# AJMG_2550XD_Silver_Jubilee.net
KiCad netlist of a schematic drawn in Altium Designer
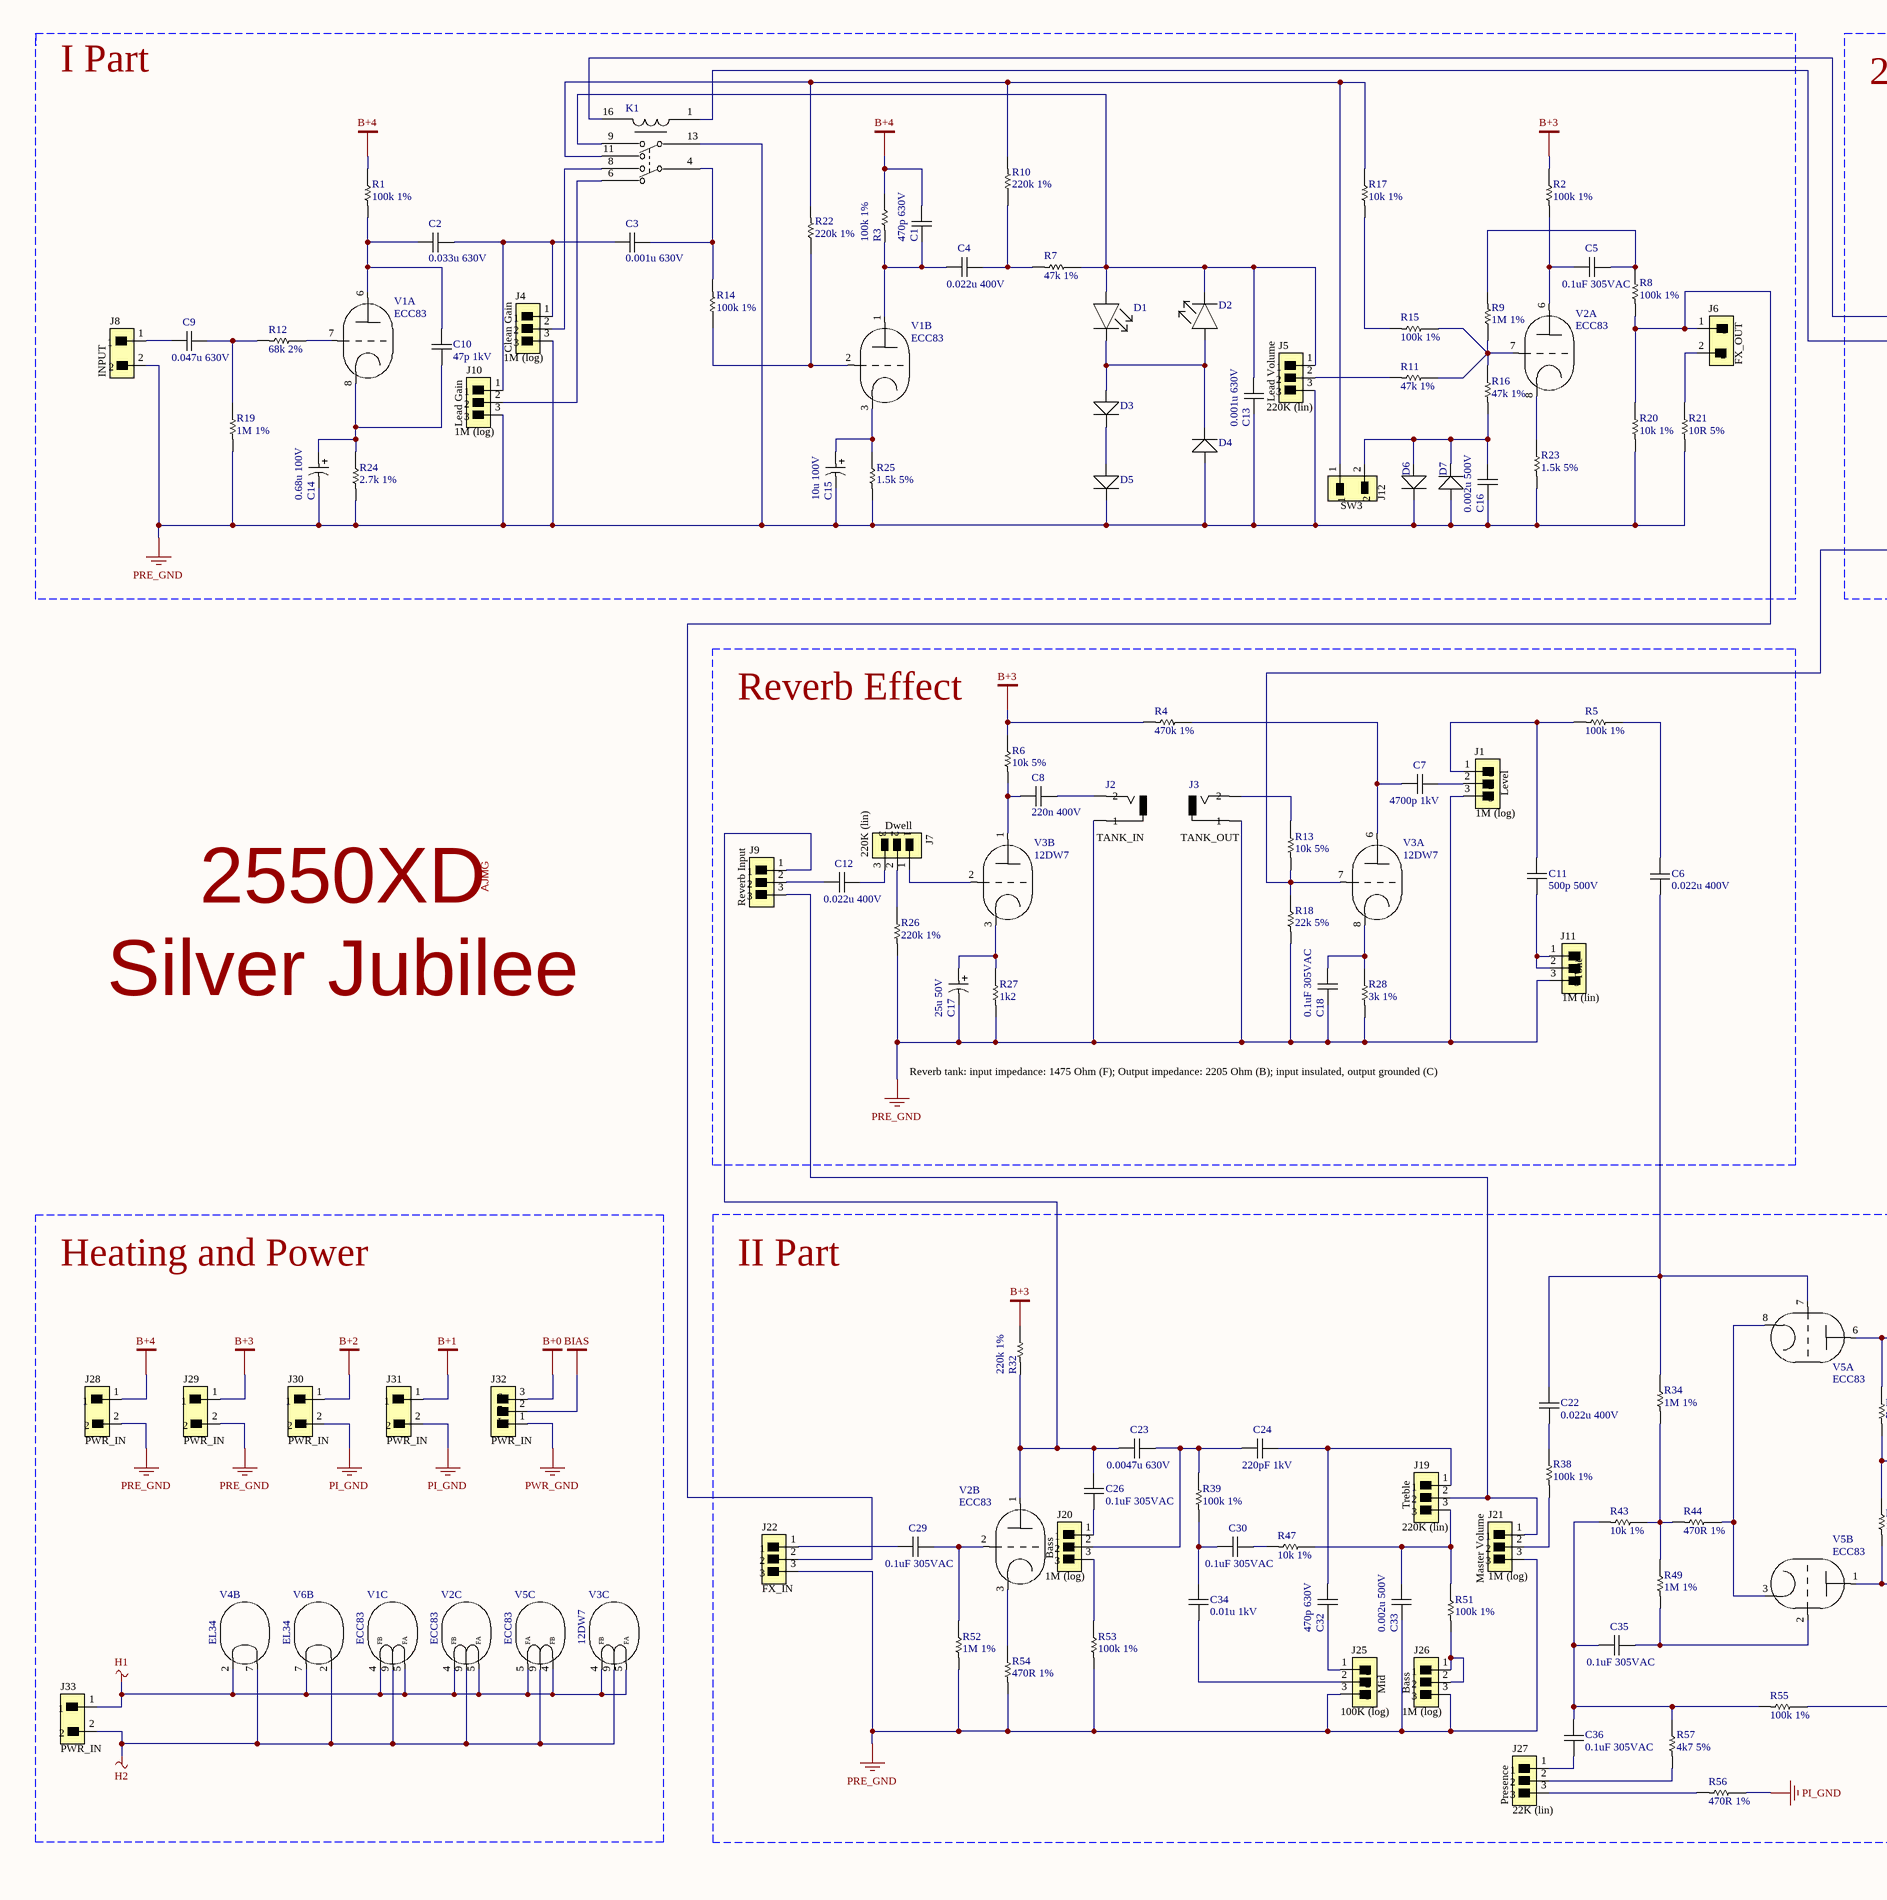
[diagram p0: AJMG 2550XD Silver Jubilee.SchDoc, left]
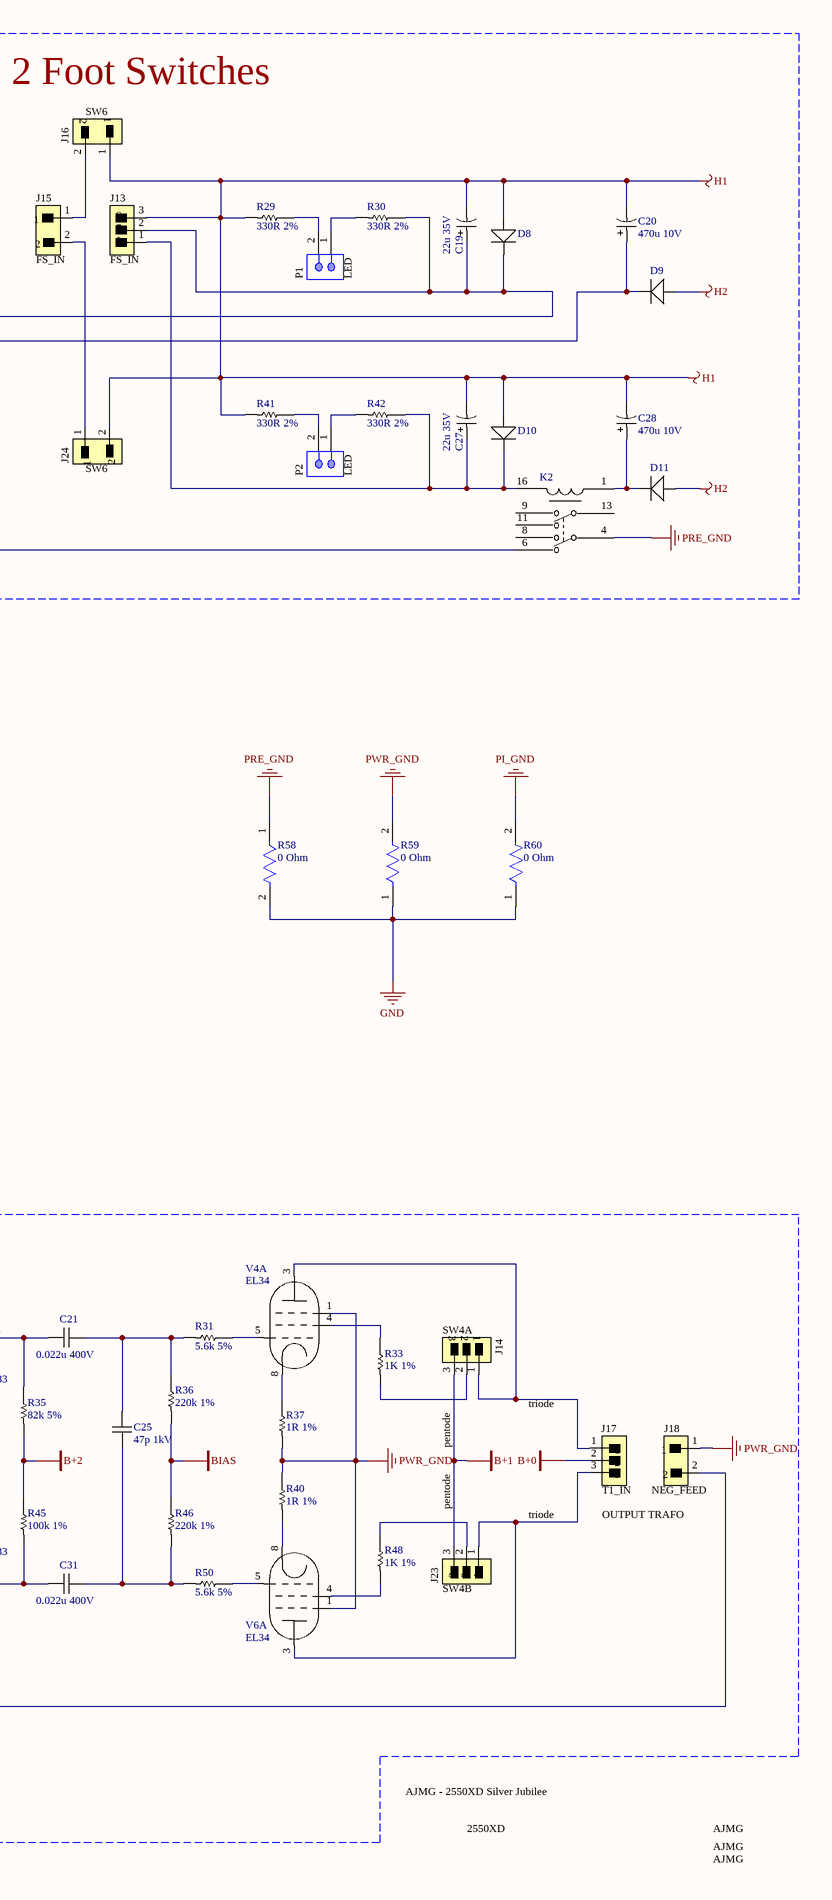
[diagram p1: AJMG 2550XD Silver Jubilee.SchDoc, right]

(export (version "E")
  (design (tool "Eeschema 10.0.6"))
  (components
    (comp (ref "C1")
      (value "470p 630V")
      (footprint "C_THT_5mm_7.2x4.5_NOT_POLARISED")
      (description "CAP FILM THT 7.2x4.5 470pF 630V 10%")
      (fields
        (field (name "MANUFACTURER") "WIMA")
        (field (name "MANUFACTURER PART NUMBER") "FKP2J004701D00KSSD")
      )
      (libsource (lib "Schematic Library - AJMG 2550XD Silver Jubilee") (part "FKP2J004701D00KSSD"))
    )
    (comp (ref "C2")
      (value "0.033u 630V")
      (footprint "C_THT_7.5mm_10.5x5_NOT_POLARISED")
      (description "CAP FILM THT 10.5x5 0.033uF 630V 5%")
      (fields
        (field (name "MANUFACTURER") "Wurth Elektronik")
        (field (name "MANUFACTURER PART NUMBER") "890303322005CS")
      )
      (libsource (lib "Schematic Library - AJMG 2550XD Silver Jubilee") (part "890303322005CS"))
    )
    (comp (ref "C3")
      (value "0.001u 630V")
      (footprint "C_THT_5mm_7.2x4.5_NOT_POLARISED")
      (description "CAP FILM THT 7.2x4.5 0.001uF 630V 10%")
      (fields
        (field (name "MANUFACTURER") "WIMA")
        (field (name "MANUFACTURER PART NUMBER") "FKP2J011001D00KI00")
      )
      (libsource (lib "Schematic Library - AJMG 2550XD Silver Jubilee") (part "FKP2J011001D00KI00"))
    )
    (comp (ref "C4")
      (value "0.022u 400V")
      (footprint "C_THT_10mm_13x5_NOT_POLARISED")
      (description "CAP FILM THT 13x4 0.022uF 400V 10%")
      (fields
        (field (name "MANUFACTURER") "WIMA")
        (field (name "MANUFACTURER PART NUMBER") "MKP4G022203C00KSSD")
      )
      (libsource (lib "Schematic Library - AJMG 2550XD Silver Jubilee") (part "MKP4G022203C00KSSD"))
    )
    (comp (ref "C5")
      (value "0.1uF 305VAC")
      (footprint "C_THT_10mm_13x5.5_NOT_POLARISED")
      (description "CAP FILM THT 13x6 0.1uF 305V(AC) 10%")
      (fields
        (field (name "MANUFACTURER") "Cornell Dubilier")
        (field (name "MANUFACTURER PART NUMBER") "MPX104K305D")
      )
      (libsource (lib "Schematic Library - AJMG 2550XD Silver Jubilee") (part "MPX104K305D"))
    )
    (comp (ref "C6")
      (value "0.022u 400V")
      (footprint "C_THT_10mm_13x5_NOT_POLARISED")
      (description "CAP FILM THT 13x4 0.022uF 400V 10%")
      (fields
        (field (name "MANUFACTURER") "WIMA")
        (field (name "MANUFACTURER PART NUMBER") "MKP4G022203C00KSSD")
      )
      (libsource (lib "Schematic Library - AJMG 2550XD Silver Jubilee") (part "MKP4G022203C00KSSD"))
    )
    (comp (ref "C7")
      (value "4700p 1kV")
      (footprint "C_THT_10mm_13x5_NOT_POLARISED")
      (description "CAP FILM THT 13x4 4700pF 1kV 10%")
      (fields
        (field (name "MANUFACTURER") "WIMA")
        (field (name "MANUFACTURER PART NUMBER") "MKP10-4700/1KV/10P10")
      )
      (libsource (lib "Schematic Library - AJMG 2550XD Silver Jubilee") (part "MKP10-4700/1KV/10P10"))
    )
    (comp (ref "C8")
      (value "220n 400V")
      (footprint "C_THT_15mm_18x5_NOT_POLARISED")
      (description "CAP FILM THT 18x5 220nF 400V 10%")
      (fields
        (field (name "MANUFACTURER") "Wurth Elektronik")
        (field (name "MANUFACTURER PART NUMBER") "890283425002CS")
      )
      (libsource (lib "Schematic Library - AJMG 2550XD Silver Jubilee") (part "890283425002CS"))
    )
    (comp (ref "C9")
      (value "0.047u 630V")
      (footprint "C_THT_7.5mm_10.5x6_NOT_POLARISED")
      (description "CAP FILM THT 10.5x6 0.047uF 630V 10%")
      (fields
        (field (name "MANUFACTURER") "Wurth Elektronik")
        (field (name "MANUFACTURER PART NUMBER") "890303422005CS")
      )
      (libsource (lib "Schematic Library - AJMG 2550XD Silver Jubilee") (part "890303422005CS"))
    )
    (comp (ref "C10")
      (value "47p 1kV")
      (footprint "C_THT_15mm_16.3x4.8_NOT_POLARISED")
      (description "CAP MICA THT 16.3x4.8 47pF 1kV 5%")
      (fields
        (field (name "MANUFACTURER") "Cornell Dubilier")
        (field (name "MANUFACTURER PART NUMBER") "CDV19EF470JO3F")
      )
      (libsource (lib "Schematic Library - AJMG 2550XD Silver Jubilee") (part "CDV19EF470JO3F"))
    )
    (comp (ref "C11")
      (value "500p 500V")
      (footprint "C_THT_9mm_16.25x5_NOT_POLARISED")
      (description "CAP MICA THT 16.3x5 500pF 500V 5%")
      (fields
        (field (name "MANUFACTURER") "Cornell Dubilier")
        (field (name "MANUFACTURER PART NUMBER") "CD19FD501JO3F")
      )
      (libsource (lib "Schematic Library - AJMG 2550XD Silver Jubilee") (part "CD19FD501JO3F"))
    )
    (comp (ref "C12")
      (value "0.022u 400V")
      (footprint "C_THT_10mm_13x5_NOT_POLARISED")
      (description "CAP FILM THT 13x4 0.022uF 400V 10%")
      (fields
        (field (name "MANUFACTURER") "WIMA")
        (field (name "MANUFACTURER PART NUMBER") "MKP4G022203C00KSSD")
      )
      (libsource (lib "Schematic Library - AJMG 2550XD Silver Jubilee") (part "MKP4G022203C00KSSD"))
    )
    (comp (ref "C13")
      (value "0.001u 630V")
      (footprint "C_THT_5mm_7.2x4.5_NOT_POLARISED")
      (description "CAP FILM THT 7.2x4.5 0.001uF 630V 10%")
      (fields
        (field (name "MANUFACTURER") "WIMA")
        (field (name "MANUFACTURER PART NUMBER") "FKP2J011001D00KI00")
      )
      (libsource (lib "Schematic Library - AJMG 2550XD Silver Jubilee") (part "FKP2J011001D00KI00"))
    )
    (comp (ref "C14")
      (value "0.68u 100V")
      (footprint "C_THT_2mm_D5H11_POLARISED")
      (description "CAP ALUM THT D5xH11 0.68uF 100V 20%")
      (fields
        (field (name "MANUFACTURER") "Nichicon")
        (field (name "MANUFACTURER PART NUMBER") "UKL2AR68KDD1TA")
      )
      (libsource (lib "Schematic Library - AJMG 2550XD Silver Jubilee") (part "UKL2AR68KDD1TA"))
    )
    (comp (ref "C15")
      (value "10u 100V")
      (footprint "C_THT_2mm_D5H11_POLARISED")
      (description "CAP ALUM THT D5xH11 10uF 100V 20%")
      (fields
        (field (name "MANUFACTURER") "Rubycon")
        (field (name "MANUFACTURER PART NUMBER") "100PK10MEFC5X11")
      )
      (libsource (lib "Schematic Library - AJMG 2550XD Silver Jubilee") (part "100PK10MEFC5X11"))
    )
    (comp (ref "C16")
      (value "0.002u 500V")
      (footprint "C_THT_8mm_16x5_NOT_POLARISED")
      (description "CAP MICA THT AxB 0.002uF 500V 5%")
      (libsource (lib "Schematic Library - AJMG 2550XD Silver Jubilee") (part "TAD SILVER MICA CAPS"))
    )
    (comp (ref "C17")
      (value "25u 50V")
      (footprint "C_THT_22.5mm_D6.35xH17.45_AXIAL_POLARISED")
      (description "CAP ALUM THT AXIAL D6.35xH17.45 25uF 50V 20%")
      (fields (field (name "MANUFACTURER") "Vishay") (field (name "MANUFACTURER PART NUMBER") "TVA1306"))
      (libsource (lib "Schematic Library - AJMG 2550XD Silver Jubilee") (part "TVA1306"))
    )
    (comp (ref "C18")
      (value "0.1uF 305VAC")
      (footprint "C_THT_10mm_13x5.5_NOT_POLARISED")
      (description "CAP FILM THT 13x6 0.1uF 305V(AC) 10%")
      (fields
        (field (name "MANUFACTURER") "Cornell Dubilier")
        (field (name "MANUFACTURER PART NUMBER") "MPX104K305D")
      )
      (libsource (lib "Schematic Library - AJMG 2550XD Silver Jubilee") (part "MPX104K305D"))
    )
    (comp (ref "C19")
      (value "22u 35V")
      (footprint "C_THT_2mm_D5H11_POLARISED")
      (description "CAP ALUM THT D5xH11 22uF 35V 20%")
      (fields
        (field (name "MANUFACTURER PART NUMBER") "860010572003")
        (field (name "MANUFACTURER") "Wurth Elektronik")
      )
      (libsource (lib "Schematic Library - AJMG 2550XD Silver Jubilee") (part "860010572003"))
    )
    (comp (ref "C20")
      (value "470u 10V")
      (footprint "C_THT_2.5mm_D6.3H11_POLARISED")
      (description "CAP ALUM THT D6.3xH11 470uF 10V 20%")
      (fields
        (field (name "MANUFACTURER PART NUMBER") "860010273011")
        (field (name "MANUFACTURER") "Wurth Elektronik")
      )
      (libsource (lib "Schematic Library - AJMG 2550XD Silver Jubilee") (part "860010273011"))
    )
    (comp (ref "C21")
      (value "0.022u 400V")
      (footprint "C_THT_10mm_13x5_NOT_POLARISED")
      (description "CAP FILM THT 13x4 0.022uF 400V 10%")
      (fields
        (field (name "MANUFACTURER") "WIMA")
        (field (name "MANUFACTURER PART NUMBER") "MKP4G022203C00KSSD")
      )
      (libsource (lib "Schematic Library - AJMG 2550XD Silver Jubilee") (part "MKP4G022203C00KSSD"))
    )
    (comp (ref "C22")
      (value "0.022u 400V")
      (footprint "C_THT_10mm_13x5_NOT_POLARISED")
      (description "CAP FILM THT 13x4 0.022uF 400V 10%")
      (fields
        (field (name "MANUFACTURER") "WIMA")
        (field (name "MANUFACTURER PART NUMBER") "MKP4G022203C00KSSD")
      )
      (libsource (lib "Schematic Library - AJMG 2550XD Silver Jubilee") (part "MKP4G022203C00KSSD"))
    )
    (comp (ref "C23")
      (value "0.0047u 630V")
      (footprint "C_THT_5mm_7.2x6.5_NOT_POLARISED")
      (description "CAP FILM THT 7.2x6.5 0.0047uF 630V 5%")
      (fields
        (field (name "MANUFACTURER") "WIMA")
        (field (name "MANUFACTURER PART NUMBER") "FKP2J014701I00JSSD")
      )
      (libsource (lib "Schematic Library - AJMG 2550XD Silver Jubilee") (part "FKP2J014701I00JSSD"))
    )
    (comp (ref "C24")
      (value "220pF 1kV")
      (footprint "C_THT_7.5mm_10.9x3.8_NOT_POLARISED")
      (description "CAP MICA THT 10.9x3.8 220pF 1kV 5%")
      (fields
        (field (name "MANUFACTURER") "Cornell Dubilier")
        (field (name "MANUFACTURER PART NUMBER") "CDV16FF221JO3F")
      )
      (libsource (lib "Schematic Library - AJMG 2550XD Silver Jubilee") (part "CDV16FF221JO3F"))
    )
    (comp (ref "C25")
      (value "47p 1kV")
      (footprint "C_THT_15mm_16.3x4.8_NOT_POLARISED")
      (description "CAP MICA THT 16.3x4.8 47pF 1kV 5%")
      (fields
        (field (name "MANUFACTURER") "Cornell Dubilier")
        (field (name "MANUFACTURER PART NUMBER") "CDV19EF470JO3F")
      )
      (libsource (lib "Schematic Library - AJMG 2550XD Silver Jubilee") (part "CDV19EF470JO3F"))
    )
    (comp (ref "C26")
      (value "0.1uF 305VAC")
      (footprint "C_THT_10mm_13x5.5_NOT_POLARISED")
      (description "CAP FILM THT 13x6 0.1uF 305V(AC) 10%")
      (fields
        (field (name "MANUFACTURER") "Cornell Dubilier")
        (field (name "MANUFACTURER PART NUMBER") "MPX104K305D")
      )
      (libsource (lib "Schematic Library - AJMG 2550XD Silver Jubilee") (part "MPX104K305D"))
    )
    (comp (ref "C27")
      (value "22u 35V")
      (footprint "C_THT_2mm_D5H11_POLARISED")
      (description "CAP ALUM THT D5xH11 22uF 35V 20%")
      (fields
        (field (name "MANUFACTURER PART NUMBER") "860010572003")
        (field (name "MANUFACTURER") "Wurth Elektronik")
      )
      (libsource (lib "Schematic Library - AJMG 2550XD Silver Jubilee") (part "860010572003"))
    )
    (comp (ref "C28")
      (value "470u 10V")
      (footprint "C_THT_2.5mm_D6.3H11_POLARISED")
      (description "CAP ALUM THT D6.3xH11 470uF 10V 20%")
      (fields
        (field (name "MANUFACTURER PART NUMBER") "860010273011")
        (field (name "MANUFACTURER") "Wurth Elektronik")
      )
      (libsource (lib "Schematic Library - AJMG 2550XD Silver Jubilee") (part "860010273011"))
    )
    (comp (ref "C29")
      (value "0.1uF 305VAC")
      (footprint "C_THT_10mm_13x5.5_NOT_POLARISED")
      (description "CAP FILM THT 13x6 0.1uF 305V(AC) 10%")
      (fields
        (field (name "MANUFACTURER") "Cornell Dubilier")
        (field (name "MANUFACTURER PART NUMBER") "MPX104K305D")
      )
      (libsource (lib "Schematic Library - AJMG 2550XD Silver Jubilee") (part "MPX104K305D"))
    )
    (comp (ref "C30")
      (value "0.1uF 305VAC")
      (footprint "C_THT_10mm_13x5.5_NOT_POLARISED")
      (description "CAP FILM THT 13x6 0.1uF 305V(AC) 10%")
      (fields
        (field (name "MANUFACTURER") "Cornell Dubilier")
        (field (name "MANUFACTURER PART NUMBER") "MPX104K305D")
      )
      (libsource (lib "Schematic Library - AJMG 2550XD Silver Jubilee") (part "MPX104K305D"))
    )
    (comp (ref "C31")
      (value "0.022u 400V")
      (footprint "C_THT_10mm_13x5_NOT_POLARISED")
      (description "CAP FILM THT 13x4 0.022uF 400V 10%")
      (fields
        (field (name "MANUFACTURER") "WIMA")
        (field (name "MANUFACTURER PART NUMBER") "MKP4G022203C00KSSD")
      )
      (libsource (lib "Schematic Library - AJMG 2550XD Silver Jubilee") (part "MKP4G022203C00KSSD"))
    )
    (comp (ref "C32")
      (value "470p 630V")
      (footprint "C_THT_5mm_7.2x4.5_NOT_POLARISED")
      (description "CAP FILM THT 7.2x4.5 470pF 630V 10%")
      (fields
        (field (name "MANUFACTURER") "WIMA")
        (field (name "MANUFACTURER PART NUMBER") "FKP2J004701D00KSSD")
      )
      (libsource (lib "Schematic Library - AJMG 2550XD Silver Jubilee") (part "FKP2J004701D00KSSD"))
    )
    (comp (ref "C33")
      (value "0.002u 500V")
      (footprint "C_THT_8mm_16x5_NOT_POLARISED")
      (description "CAP MICA THT AxB 0.002uF 500V 5%")
      (libsource (lib "Schematic Library - AJMG 2550XD Silver Jubilee") (part "TAD SILVER MICA CAPS"))
    )
    (comp (ref "C34")
      (value "0.01u 1kV")
      (footprint "C_THT_7.5mm_10.5x6_NOT_POLARISED")
      (description "CAP FILM THT 10.5x6 0.01uF 1kV 10%")
      (fields
        (field (name "MANUFACTURER") "Wurth Elektronik")
        (field (name "MANUFACTURER PART NUMBER") "890493422002CS")
      )
      (libsource (lib "Schematic Library - AJMG 2550XD Silver Jubilee") (part "890493422002CS"))
    )
    (comp (ref "C35")
      (value "0.1uF 305VAC")
      (footprint "C_THT_10mm_13x5.5_NOT_POLARISED")
      (description "CAP FILM THT 13x6 0.1uF 305V(AC) 10%")
      (fields
        (field (name "MANUFACTURER") "Cornell Dubilier")
        (field (name "MANUFACTURER PART NUMBER") "MPX104K305D")
      )
      (libsource (lib "Schematic Library - AJMG 2550XD Silver Jubilee") (part "MPX104K305D"))
    )
    (comp (ref "C36")
      (value "0.1uF 305VAC")
      (footprint "C_THT_10mm_13x5.5_NOT_POLARISED")
      (description "CAP FILM THT 13x6 0.1uF 305V(AC) 10%")
      (fields
        (field (name "MANUFACTURER") "Cornell Dubilier")
        (field (name "MANUFACTURER PART NUMBER") "MPX104K305D")
      )
      (libsource (lib "Schematic Library - AJMG 2550XD Silver Jubilee") (part "MPX104K305D"))
    )
    (comp (ref "D1")
      (value "LTST-C930CKT")
      (footprint "D_LTST-C930CKT")
      (description "DIODE LED SMD")
      (fields
        (field (name "OCTOPART") "https://octopart.com/ltst-c930kskt-lite-on-549925")
        (field (name "MANUFACTURER PART NUMBER") "LTST-C930KSKT")
      )
      (libsource (lib "Schematic Library - AJMG 2550XD Silver Jubilee") (part "LTST-C930CKT"))
    )
    (comp (ref "D2")
      (value "LTST-C930CKT")
      (footprint "D_LTST-C930CKT")
      (description "DIODE LED SMD")
      (fields
        (field (name "OCTOPART") "https://octopart.com/ltst-c930kskt-lite-on-549925")
        (field (name "MANUFACTURER PART NUMBER") "LTST-C930KSKT")
      )
      (libsource (lib "Schematic Library - AJMG 2550XD Silver Jubilee") (part "LTST-C930CKT"))
    )
    (comp (ref "D3")
      (value "1N4007-T")
      (footprint "D_1N4007-T")
      (description "DIODE\r\n1.0 A Rectifier, 8 pF, 1000 V, -65 to 150 degC, 2-Pin DO-41 Plastic, RoHS, Tape and Reel")
      (fields (field (name "MANUFACTURER") "Diodes Inc"))
      (libsource (lib "Schematic Library - AJMG 2550XD Silver Jubilee") (part "1N4007-T"))
    )
    (comp (ref "D4")
      (value "1N4007-T")
      (footprint "D_1N4007-T")
      (description "DIODE\r\n1.0 A Rectifier, 8 pF, 1000 V, -65 to 150 degC, 2-Pin DO-41 Plastic, RoHS, Tape and Reel")
      (fields (field (name "MANUFACTURER") "Diodes Inc"))
      (libsource (lib "Schematic Library - AJMG 2550XD Silver Jubilee") (part "1N4007-T"))
    )
    (comp (ref "D5")
      (value "1N4007-T")
      (footprint "D_1N4007-T")
      (description "DIODE\r\n1.0 A Rectifier, 8 pF, 1000 V, -65 to 150 degC, 2-Pin DO-41 Plastic, RoHS, Tape and Reel")
      (fields (field (name "MANUFACTURER") "Diodes Inc"))
      (libsource (lib "Schematic Library - AJMG 2550XD Silver Jubilee") (part "1N4007-T"))
    )
    (comp (ref "D6")
      (value "1N4007-T")
      (footprint "D_1N4007-T")
      (description "DIODE\r\n1.0 A Rectifier, 8 pF, 1000 V, -65 to 150 degC, 2-Pin DO-41 Plastic, RoHS, Tape and Reel")
      (fields (field (name "MANUFACTURER") "Diodes Inc"))
      (libsource (lib "Schematic Library - AJMG 2550XD Silver Jubilee") (part "1N4007-T"))
    )
    (comp (ref "D7")
      (value "1N4007-T")
      (footprint "D_1N4007-T")
      (description "DIODE\r\n1.0 A Rectifier, 8 pF, 1000 V, -65 to 150 degC, 2-Pin DO-41 Plastic, RoHS, Tape and Reel")
      (fields (field (name "MANUFACTURER") "Diodes Inc"))
      (libsource (lib "Schematic Library - AJMG 2550XD Silver Jubilee") (part "1N4007-T"))
    )
    (comp (ref "D8")
      (value "1N4007-T")
      (footprint "D_1N4007-T")
      (description "DIODE\r\n1.0 A Rectifier, 8 pF, 1000 V, -65 to 150 degC, 2-Pin DO-41 Plastic, RoHS, Tape and Reel")
      (fields (field (name "MANUFACTURER") "Diodes Inc"))
      (libsource (lib "Schematic Library - AJMG 2550XD Silver Jubilee") (part "1N4007-T"))
    )
    (comp (ref "D9")
      (value "1N4007-T")
      (footprint "D_1N4007-T")
      (description "DIODE\r\n1.0 A Rectifier, 8 pF, 1000 V, -65 to 150 degC, 2-Pin DO-41 Plastic, RoHS, Tape and Reel")
      (fields (field (name "MANUFACTURER") "Diodes Inc"))
      (libsource (lib "Schematic Library - AJMG 2550XD Silver Jubilee") (part "1N4007-T"))
    )
    (comp (ref "D10")
      (value "1N4007-T")
      (footprint "D_1N4007-T")
      (description "DIODE\r\n1.0 A Rectifier, 8 pF, 1000 V, -65 to 150 degC, 2-Pin DO-41 Plastic, RoHS, Tape and Reel")
      (fields (field (name "MANUFACTURER") "Diodes Inc"))
      (libsource (lib "Schematic Library - AJMG 2550XD Silver Jubilee") (part "1N4007-T"))
    )
    (comp (ref "D11")
      (value "1N4007-T")
      (footprint "D_1N4007-T")
      (description "DIODE\r\n1.0 A Rectifier, 8 pF, 1000 V, -65 to 150 degC, 2-Pin DO-41 Plastic, RoHS, Tape and Reel")
      (fields (field (name "MANUFACTURER") "Diodes Inc"))
      (libsource (lib "Schematic Library - AJMG 2550XD Silver Jubilee") (part "1N4007-T"))
    )
    (comp (ref "J1")
      (value "43650-0320")
      (footprint "CONN HEADER VERT 3POS 3MM")
      (description "CONN HEADER VERT 3POS 3MM")
      (fields
        (field (name "MANUFACTURER") "Molex")
        (field (name "OCTOPART") "https://octopart.com/43650-0320-molex-7670312")
      )
      (libsource (lib "") (part "CMP-04776-000004-1_1"))
    )
    (comp (ref "J2")
      (value "RCJ-021")
      (footprint "CONN_CUI_RCJ-021")
      (description "CONN RCA JACK MONO 3.2MM PCB")
      (fields (field (name "MANUFACTURER") "CUI"))
      (libsource (lib "Schematic Library - AJMG 2550XD Silver Jubilee") (part "RCJ-021"))
    )
    (comp (ref "J3")
      (value "RCJ-021")
      (footprint "CONN_CUI_RCJ-021")
      (description "CONN RCA JACK MONO 3.2MM PCB")
      (fields (field (name "MANUFACTURER") "CUI"))
      (libsource (lib "") (part "RCJ-021_1"))
    )
    (comp (ref "J4")
      (value "43650-0320")
      (footprint "CONN HEADER VERT 3POS 3MM")
      (description "CONN HEADER VERT 3POS 3MM")
      (fields
        (field (name "MANUFACTURER") "Molex")
        (field (name "OCTOPART") "https://octopart.com/43650-0320-molex-7670312")
      )
      (libsource (lib "Schematic Library - AJMG 2550XD Silver Jubilee") (part "CMP-04776-000004-1"))
    )
    (comp (ref "J5")
      (value "43650-0320")
      (footprint "CONN HEADER VERT 3POS 3MM")
      (description "CONN HEADER VERT 3POS 3MM")
      (fields
        (field (name "MANUFACTURER") "Molex")
        (field (name "OCTOPART") "https://octopart.com/43650-0320-molex-7670312")
      )
      (libsource (lib "Schematic Library - AJMG 2550XD Silver Jubilee") (part "CMP-04776-000004-1"))
    )
    (comp (ref "J6")
      (value "43650-0229")
      (footprint "CONN HEADER VERT 2POS 3MM")
      (description "CONN HEADER VERT 2POS 3MM")
      (fields
        (field (name "OCTOPART") "https://octopart.com/43650-0229-molex-7652326")
        (field (name "MANUFACTURER") "Molex")
      )
      (libsource (lib "") (part "CMP-04776-000041-1_1"))
    )
    (comp (ref "J7")
      (value "43650-0320")
      (footprint "CONN HEADER VERT 3POS 3MM")
      (description "CONN HEADER VERT 3POS 3MM")
      (fields
        (field (name "MANUFACTURER") "Molex")
        (field (name "OCTOPART") "https://octopart.com/43650-0320-molex-7670312")
      )
      (libsource (lib "") (part "CMP-04776-000004-1_1"))
    )
    (comp (ref "J8")
      (value "43650-0229")
      (footprint "CONN HEADER VERT 2POS 3MM")
      (description "CONN HEADER VERT 2POS 3MM")
      (fields
        (field (name "OCTOPART") "https://octopart.com/43650-0229-molex-7652326")
        (field (name "MANUFACTURER") "Molex")
      )
      (libsource (lib "Schematic Library - AJMG 2550XD Silver Jubilee") (part "CMP-04776-000041-1"))
    )
    (comp (ref "J9")
      (value "43650-0320")
      (footprint "CONN HEADER VERT 3POS 3MM")
      (description "CONN HEADER VERT 3POS 3MM")
      (fields
        (field (name "MANUFACTURER") "Molex")
        (field (name "OCTOPART") "https://octopart.com/43650-0320-molex-7670312")
      )
      (libsource (lib "Schematic Library - AJMG 2550XD Silver Jubilee") (part "CMP-04776-000004-1"))
    )
    (comp (ref "J10")
      (value "43650-0320")
      (footprint "CONN HEADER VERT 3POS 3MM")
      (description "CONN HEADER VERT 3POS 3MM")
      (fields
        (field (name "MANUFACTURER") "Molex")
        (field (name "OCTOPART") "https://octopart.com/43650-0320-molex-7670312")
      )
      (libsource (lib "Schematic Library - AJMG 2550XD Silver Jubilee") (part "CMP-04776-000004-1"))
    )
    (comp (ref "J11")
      (value "43650-0320")
      (footprint "CONN HEADER VERT 3POS 3MM")
      (description "CONN HEADER VERT 3POS 3MM")
      (fields
        (field (name "MANUFACTURER") "Molex")
        (field (name "OCTOPART") "https://octopart.com/43650-0320-molex-7670312")
      )
      (libsource (lib "") (part "CMP-04776-000004-1_1"))
    )
    (comp (ref "J12")
      (value "43650-0229")
      (footprint "CONN HEADER VERT 2POS 3MM")
      (description "CONN HEADER VERT 2POS 3MM")
      (fields
        (field (name "OCTOPART") "https://octopart.com/43650-0229-molex-7652326")
        (field (name "MANUFACTURER") "Molex")
      )
      (libsource (lib "") (part "CMP-04776-000041-1_2"))
    )
    (comp (ref "J13")
      (value "43650-0320")
      (footprint "CONN HEADER VERT 3POS 3MM")
      (description "CONN HEADER VERT 3POS 3MM")
      (fields
        (field (name "MANUFACTURER") "Molex")
        (field (name "OCTOPART") "https://octopart.com/43650-0320-molex-7670312")
      )
      (libsource (lib "") (part "CMP-04776-000004-1_2"))
    )
    (comp (ref "J14")
      (value "43650-0320")
      (footprint "CONN HEADER VERT 3POS 3MM")
      (description "CONN HEADER VERT 3POS 3MM")
      (fields
        (field (name "MANUFACTURER") "Molex")
        (field (name "OCTOPART") "https://octopart.com/43650-0320-molex-7670312")
      )
      (libsource (lib "") (part "CMP-04776-000004-1_1"))
    )
    (comp (ref "J15")
      (value "43650-0229")
      (footprint "CONN HEADER VERT 2POS 3MM")
      (description "CONN HEADER VERT 2POS 3MM")
      (fields
        (field (name "OCTOPART") "https://octopart.com/43650-0229-molex-7652326")
        (field (name "MANUFACTURER") "Molex")
      )
      (libsource (lib "Schematic Library - AJMG 2550XD Silver Jubilee") (part "CMP-04776-000041-1"))
    )
    (comp (ref "J16")
      (value "43650-0229")
      (footprint "CONN HEADER VERT 2POS 3MM")
      (description "CONN HEADER VERT 2POS 3MM")
      (fields
        (field (name "OCTOPART") "https://octopart.com/43650-0229-molex-7652326")
        (field (name "MANUFACTURER") "Molex")
      )
      (libsource (lib "") (part "CMP-04776-000041-1_1"))
    )
    (comp (ref "J17")
      (value "43650-0320")
      (footprint "CONN HEADER VERT 3POS 3MM")
      (description "CONN HEADER VERT 3POS 3MM")
      (fields
        (field (name "MANUFACTURER") "Molex")
        (field (name "OCTOPART") "https://octopart.com/43650-0320-molex-7670312")
      )
      (libsource (lib "") (part "CMP-04776-000004-1_1"))
    )
    (comp (ref "J18")
      (value "43650-0229")
      (footprint "CONN HEADER VERT 2POS 3MM")
      (description "CONN HEADER VERT 2POS 3MM")
      (fields
        (field (name "OCTOPART") "https://octopart.com/43650-0229-molex-7652326")
        (field (name "MANUFACTURER") "Molex")
      )
      (libsource (lib "Schematic Library - AJMG 2550XD Silver Jubilee") (part "CMP-04776-000041-1"))
    )
    (comp (ref "J19")
      (value "43650-0320")
      (footprint "CONN HEADER VERT 3POS 3MM")
      (description "CONN HEADER VERT 3POS 3MM")
      (fields
        (field (name "MANUFACTURER") "Molex")
        (field (name "OCTOPART") "https://octopart.com/43650-0320-molex-7670312")
      )
      (libsource (lib "Schematic Library - AJMG 2550XD Silver Jubilee") (part "CMP-04776-000004-1"))
    )
    (comp (ref "J20")
      (value "43650-0320")
      (footprint "CONN HEADER VERT 3POS 3MM")
      (description "CONN HEADER VERT 3POS 3MM")
      (fields
        (field (name "MANUFACTURER") "Molex")
        (field (name "OCTOPART") "https://octopart.com/43650-0320-molex-7670312")
      )
      (libsource (lib "Schematic Library - AJMG 2550XD Silver Jubilee") (part "CMP-04776-000004-1"))
    )
    (comp (ref "J21")
      (value "43650-0320")
      (footprint "CONN HEADER VERT 3POS 3MM")
      (description "CONN HEADER VERT 3POS 3MM")
      (fields
        (field (name "MANUFACTURER") "Molex")
        (field (name "OCTOPART") "https://octopart.com/43650-0320-molex-7670312")
      )
      (libsource (lib "Schematic Library - AJMG 2550XD Silver Jubilee") (part "CMP-04776-000004-1"))
    )
    (comp (ref "J22")
      (value "43650-0320")
      (footprint "CONN HEADER VERT 3POS 3MM")
      (description "CONN HEADER VERT 3POS 3MM")
      (fields
        (field (name "MANUFACTURER") "Molex")
        (field (name "OCTOPART") "https://octopart.com/43650-0320-molex-7670312")
      )
      (libsource (lib "Schematic Library - AJMG 2550XD Silver Jubilee") (part "CMP-04776-000004-1"))
    )
    (comp (ref "J23")
      (value "43650-0320")
      (footprint "CONN HEADER VERT 3POS 3MM")
      (description "CONN HEADER VERT 3POS 3MM")
      (fields
        (field (name "MANUFACTURER") "Molex")
        (field (name "OCTOPART") "https://octopart.com/43650-0320-molex-7670312")
      )
      (libsource (lib "Schematic Library - AJMG 2550XD Silver Jubilee") (part "CMP-04776-000004-1"))
    )
    (comp (ref "J24")
      (value "43650-0229")
      (footprint "CONN HEADER VERT 2POS 3MM")
      (description "CONN HEADER VERT 2POS 3MM")
      (fields
        (field (name "OCTOPART") "https://octopart.com/43650-0229-molex-7652326")
        (field (name "MANUFACTURER") "Molex")
      )
      (libsource (lib "") (part "CMP-04776-000041-1_2"))
    )
    (comp (ref "J25")
      (value "43650-0320")
      (footprint "CONN HEADER VERT 3POS 3MM")
      (description "CONN HEADER VERT 3POS 3MM")
      (fields
        (field (name "MANUFACTURER") "Molex")
        (field (name "OCTOPART") "https://octopart.com/43650-0320-molex-7670312")
      )
      (libsource (lib "") (part "CMP-04776-000004-1_1"))
    )
    (comp (ref "J26")
      (value "43650-0320")
      (footprint "CONN HEADER VERT 3POS 3MM")
      (description "CONN HEADER VERT 3POS 3MM")
      (fields
        (field (name "MANUFACTURER") "Molex")
        (field (name "OCTOPART") "https://octopart.com/43650-0320-molex-7670312")
      )
      (libsource (lib "Schematic Library - AJMG 2550XD Silver Jubilee") (part "CMP-04776-000004-1"))
    )
    (comp (ref "J27")
      (value "43650-0320")
      (footprint "CONN HEADER VERT 3POS 3MM")
      (description "CONN HEADER VERT 3POS 3MM")
      (fields
        (field (name "MANUFACTURER") "Molex")
        (field (name "OCTOPART") "https://octopart.com/43650-0320-molex-7670312")
      )
      (libsource (lib "Schematic Library - AJMG 2550XD Silver Jubilee") (part "CMP-04776-000004-1"))
    )
    (comp (ref "J28")
      (value "43650-0229")
      (footprint "CONN HEADER VERT 2POS 3MM")
      (description "CONN HEADER VERT 2POS 3MM")
      (fields
        (field (name "OCTOPART") "https://octopart.com/43650-0229-molex-7652326")
        (field (name "MANUFACTURER") "Molex")
      )
      (libsource (lib "Schematic Library - AJMG 2550XD Silver Jubilee") (part "CMP-04776-000041-1"))
    )
    (comp (ref "J29")
      (value "43650-0229")
      (footprint "CONN HEADER VERT 2POS 3MM")
      (description "CONN HEADER VERT 2POS 3MM")
      (fields
        (field (name "OCTOPART") "https://octopart.com/43650-0229-molex-7652326")
        (field (name "MANUFACTURER") "Molex")
      )
      (libsource (lib "Schematic Library - AJMG 2550XD Silver Jubilee") (part "CMP-04776-000041-1"))
    )
    (comp (ref "J30")
      (value "43650-0229")
      (footprint "CONN HEADER VERT 2POS 3MM")
      (description "CONN HEADER VERT 2POS 3MM")
      (fields
        (field (name "OCTOPART") "https://octopart.com/43650-0229-molex-7652326")
        (field (name "MANUFACTURER") "Molex")
      )
      (libsource (lib "Schematic Library - AJMG 2550XD Silver Jubilee") (part "CMP-04776-000041-1"))
    )
    (comp (ref "J31")
      (value "43650-0229")
      (footprint "CONN HEADER VERT 2POS 3MM")
      (description "CONN HEADER VERT 2POS 3MM")
      (fields
        (field (name "OCTOPART") "https://octopart.com/43650-0229-molex-7652326")
        (field (name "MANUFACTURER") "Molex")
      )
      (libsource (lib "Schematic Library - AJMG 2550XD Silver Jubilee") (part "CMP-04776-000041-1"))
    )
    (comp (ref "J32")
      (value "43650-0320")
      (footprint "CONN HEADER VERT 3POS 3MM")
      (description "CONN HEADER VERT 3POS 3MM")
      (fields
        (field (name "MANUFACTURER") "Molex")
        (field (name "OCTOPART") "https://octopart.com/43650-0320-molex-7670312")
      )
      (libsource (lib "") (part "CMP-04776-000004-1_2"))
    )
    (comp (ref "J33")
      (value "43650-0229")
      (footprint "CONN HEADER VERT 2POS 3MM")
      (description "CONN HEADER VERT 2POS 3MM")
      (fields
        (field (name "OCTOPART") "https://octopart.com/43650-0229-molex-7652326")
        (field (name "MANUFACTURER") "Molex")
      )
      (libsource (lib "Schematic Library - AJMG 2550XD Silver Jubilee") (part "CMP-04776-000041-1"))
    )
    (comp (ref "K1")
      (value "9-1393792-3")
      (footprint "RELAY_V23105A5301A201")
      (description "RELAY TELECOM DPDT 3A 5V")
      (fields
        (field (name "MANUFACTURER") "TE Connectivity")
        (field (name "OCTOPART") "https://octopart.com/9-1393792-3-te+connectivity-41192813")
      )
      (libsource (lib "Schematic Library - AJMG 2550XD Silver Jubilee") (part "CMP-03395-000111-1"))
    )
    (comp (ref "K2")
      (value "9-1393792-3")
      (footprint "RELAY_V23105A5301A201")
      (description "RELAY TELECOM DPDT 3A 5V")
      (fields
        (field (name "MANUFACTURER") "TE Connectivity")
        (field (name "OCTOPART") "https://octopart.com/9-1393792-3-te+connectivity-41192813")
      )
      (libsource (lib "Schematic Library - AJMG 2550XD Silver Jubilee") (part "CMP-03395-000111-1"))
    )
    (comp (ref "P1")
      (value "22-27-2021")
      (footprint "MOLX-22-27-2021_V")
      (fields (field (name "MANUFACTURER") "Molex") (field (name "PARTNUMBER") "0022272021"))
      (libsource (lib "Altium Content Vault") (part "CN-1P-M-R2"))
    )
    (comp (ref "P2")
      (value "22-27-2021")
      (footprint "MOLX-22-27-2021_V")
      (fields (field (name "MANUFACTURER") "Molex") (field (name "PARTNUMBER") "0022272021"))
      (libsource (lib "Altium Content Vault") (part "CN-1P-M-R2"))
    )
    (comp (ref "R1")
      (value "100k 1%")
      (footprint "R_2010")
      (description "RES SMD 2010 100K 1% 1W")
      (fields
        (field (name "MANUFACTURER") "Bourns")
        (field (name "MANUFACTURER PART NUMBER") "CMP2010-FX-1003ELF")
      )
      (libsource (lib "Schematic Library - AJMG 2550XD Silver Jubilee") (part "CMP2010-FX-1003ELF"))
    )
    (comp (ref "R2")
      (value "100k 1%")
      (footprint "R_2010")
      (description "RES SMD 2010 100K 1% 1W")
      (fields
        (field (name "MANUFACTURER") "Bourns")
        (field (name "MANUFACTURER PART NUMBER") "CMP2010-FX-1003ELF")
      )
      (libsource (lib "Schematic Library - AJMG 2550XD Silver Jubilee") (part "CMP2010-FX-1003ELF"))
    )
    (comp (ref "R3")
      (value "100k 1%")
      (footprint "R_2010")
      (description "RES SMD 2010 100K 1% 1W")
      (fields
        (field (name "MANUFACTURER") "Bourns")
        (field (name "MANUFACTURER PART NUMBER") "CMP2010-FX-1003ELF")
      )
      (libsource (lib "Schematic Library - AJMG 2550XD Silver Jubilee") (part "CMP2010-FX-1003ELF"))
    )
    (comp (ref "R4")
      (value "470k 1%")
      (footprint "R_2010")
      (description "RES SMD 2010 470K 1% 1W")
      (libsource (lib "Schematic Library - AJMG 2550XD Silver Jubilee") (part "CRM2010-FX-4703ELF"))
    )
    (comp (ref "R5")
      (value "100k 1%")
      (footprint "R_2010")
      (description "RES SMD 2010 100K 1% 1W")
      (fields
        (field (name "MANUFACTURER") "Bourns")
        (field (name "MANUFACTURER PART NUMBER") "CMP2010-FX-1003ELF")
      )
      (libsource (lib "Schematic Library - AJMG 2550XD Silver Jubilee") (part "CMP2010-FX-1003ELF"))
    )
    (comp (ref "R6")
      (value "10k 5%")
      (footprint "R_2512")
      (description "RES SMD 2512 10K 5% 3W")
      (fields
        (field (name "MANUFACTURER") "Bourns")
        (field (name "MANUFACTURER PART NUMBER") "CHP2512-JW-103ELF")
      )
      (libsource (lib "Schematic Library - AJMG 2550XD Silver Jubilee") (part "CHP2512-JW-103ELF"))
    )
    (comp (ref "R7")
      (value "47k 1%")
      (footprint "R_2512")
      (description "RES SMD 2512 47K 1% 1.5W")
      (fields
        (field (name "MANUFACTURER") "Bourns")
        (field (name "MANUFACTURER PART NUMBER") "CMP2512-FX-4702ELF")
      )
      (libsource (lib "Schematic Library - AJMG 2550XD Silver Jubilee") (part "CMP2512-FX-4702ELF"))
    )
    (comp (ref "R8")
      (value "100k 1%")
      (footprint "R_2010")
      (description "RES SMD 2010 100K 1% 1W")
      (fields
        (field (name "MANUFACTURER") "Bourns")
        (field (name "MANUFACTURER PART NUMBER") "CMP2010-FX-1003ELF")
      )
      (libsource (lib "Schematic Library - AJMG 2550XD Silver Jubilee") (part "CMP2010-FX-1003ELF"))
    )
    (comp (ref "R9")
      (value "1M 1%")
      (footprint "R_2010")
      (description "RES SMD 2010 1M 1% 1W")
      (fields
        (field (name "MANUFACTURER") "Bourns")
        (field (name "MANUFACTURER PART NUMBER") "CMP2010-FX-1004ELF")
      )
      (libsource (lib "Schematic Library - AJMG 2550XD Silver Jubilee") (part "CMP2010-FX-1004ELF"))
    )
    (comp (ref "R10")
      (value "220k 1%")
      (footprint "R_2010")
      (description "RES SMD 2010 220K 1% 1/2W")
      (fields
        (field (name "MANUFACTURER") "Bourns JW Miller")
        (field (name "MANUFACTURER PART NUMBER") "CHV2010-FX-2203ELF")
      )
      (libsource (lib "Schematic Library - AJMG 2550XD Silver Jubilee") (part "CHV2010-FX-2203ELF"))
    )
    (comp (ref "R11")
      (value "47k 1%")
      (footprint "R_2512")
      (description "RES SMD 2512 47K 1% 1.5W")
      (fields
        (field (name "MANUFACTURER") "Bourns")
        (field (name "MANUFACTURER PART NUMBER") "CMP2512-FX-4702ELF")
      )
      (libsource (lib "Schematic Library - AJMG 2550XD Silver Jubilee") (part "CMP2512-FX-4702ELF"))
    )
    (comp (ref "R12")
      (value "68k 2%")
      (footprint "R_MELF_0204")
      (description "RES SMD 0204 68K 2% 400mW")
      (fields
        (field (name "MANUFACTURER") "Vishay Beyschlag")
        (field (name "MANUFACTURER PART NUMBER") "CMA02040X6802GB300")
      )
      (libsource (lib "Schematic Library - AJMG 2550XD Silver Jubilee") (part "CMA02040X6802GB300"))
    )
    (comp (ref "R13")
      (value "10k 5%")
      (footprint "R_2512")
      (description "RES SMD 2512 10K 5% 3W")
      (fields
        (field (name "MANUFACTURER") "Bourns")
        (field (name "MANUFACTURER PART NUMBER") "CHP2512-JW-103ELF")
      )
      (libsource (lib "Schematic Library - AJMG 2550XD Silver Jubilee") (part "CHP2512-JW-103ELF"))
    )
    (comp (ref "R14")
      (value "100k 1%")
      (footprint "R_2010")
      (description "RES SMD 2010 100K 1% 1W")
      (fields
        (field (name "MANUFACTURER") "Bourns")
        (field (name "MANUFACTURER PART NUMBER") "CMP2010-FX-1003ELF")
      )
      (libsource (lib "Schematic Library - AJMG 2550XD Silver Jubilee") (part "CMP2010-FX-1003ELF"))
    )
    (comp (ref "R15")
      (value "100k 1%")
      (footprint "R_2010")
      (description "RES SMD 2010 100K 1% 1W")
      (fields
        (field (name "MANUFACTURER") "Bourns")
        (field (name "MANUFACTURER PART NUMBER") "CMP2010-FX-1003ELF")
      )
      (libsource (lib "Schematic Library - AJMG 2550XD Silver Jubilee") (part "CMP2010-FX-1003ELF"))
    )
    (comp (ref "R16")
      (value "47k 1%")
      (footprint "R_2512")
      (description "RES SMD 2512 47K 1% 1.5W")
      (fields
        (field (name "MANUFACTURER") "Bourns")
        (field (name "MANUFACTURER PART NUMBER") "CMP2512-FX-4702ELF")
      )
      (libsource (lib "Schematic Library - AJMG 2550XD Silver Jubilee") (part "CMP2512-FX-4702ELF"))
    )
    (comp (ref "R17")
      (value "10k 1%")
      (footprint "R_2010")
      (description "RES SMD 2010 10K 1% 1W")
      (fields
        (field (name "MANUFACTURER") "Bourns")
        (field (name "MANUFACTURER PART NUMBER") "CMP2010-FX-1002ELF")
      )
      (libsource (lib "Schematic Library - AJMG 2550XD Silver Jubilee") (part "CMP2010-FX-1002ELF"))
    )
    (comp (ref "R18")
      (value "22k 5%")
      (footprint "R_2512")
      (description "RES SMD 2512 22K 5% 1W")
      (fields
        (field (name "MANUFACTURER") "Bourns")
        (field (name "MANUFACTURER PART NUMBER") "CR2512-JW-223ELF")
      )
      (libsource (lib "Schematic Library - AJMG 2550XD Silver Jubilee") (part "CR2512-JW-223ELF"))
    )
    (comp (ref "R19")
      (value "1M 1%")
      (footprint "R_2010")
      (description "RES SMD 2010 1M 1% 1W")
      (fields
        (field (name "MANUFACTURER") "Bourns")
        (field (name "MANUFACTURER PART NUMBER") "CMP2010-FX-1004ELF")
      )
      (libsource (lib "Schematic Library - AJMG 2550XD Silver Jubilee") (part "CMP2010-FX-1004ELF"))
    )
    (comp (ref "R20")
      (value "10k 1%")
      (footprint "R_2010")
      (description "RES SMD 2010 10K 1% 1W")
      (fields
        (field (name "MANUFACTURER") "Bourns")
        (field (name "MANUFACTURER PART NUMBER") "CMP2010-FX-1002ELF")
      )
      (libsource (lib "Schematic Library - AJMG 2550XD Silver Jubilee") (part "CMP2010-FX-1002ELF"))
    )
    (comp (ref "R21")
      (value "10R 5%")
      (footprint "R_2616_MOLDED")
      (description "RES SMD 2616 10R 5% 2W SMW2")
      (fields
        (field (name "MANUFACTURER") "TE Connectivity")
        (field (name "MANUFACTURER PART NUMBER") "SMW210RJT")
      )
      (libsource (lib "Schematic Library - AJMG 2550XD Silver Jubilee") (part "SMW210RJT"))
    )
    (comp (ref "R22")
      (value "220k 1%")
      (footprint "R_2010")
      (description "RES SMD 2010 220K 1% 1/2W")
      (fields
        (field (name "MANUFACTURER") "Bourns JW Miller")
        (field (name "MANUFACTURER PART NUMBER") "CHV2010-FX-2203ELF")
      )
      (libsource (lib "Schematic Library - AJMG 2550XD Silver Jubilee") (part "CHV2010-FX-2203ELF"))
    )
    (comp (ref "R23")
      (value "1.5k 5%")
      (footprint "R_2512")
      (description "RES SMD 2512 1.5k 5% 1W")
      (fields
        (field (name "MANUFACTURER") "Bourns")
        (field (name "MANUFACTURER PART NUMBER") "CR2512-JW-152ELF")
      )
      (libsource (lib "Schematic Library - AJMG 2550XD Silver Jubilee") (part "CR2512-JW-152ELF"))
    )
    (comp (ref "R24")
      (value "2.7k 1%")
      (footprint "R_2512")
      (description "RES SMD 2512 2.7K 1% 1.5W")
      (fields
        (field (name "MANUFACTURER") "Bourns")
        (field (name "MANUFACTURER PART NUMBER") "CMP2512AFX-2701ELF")
      )
      (libsource (lib "Schematic Library - AJMG 2550XD Silver Jubilee") (part "CMP2512AFX-2701ELF"))
    )
    (comp (ref "R25")
      (value "1.5k 5%")
      (footprint "R_2512")
      (description "RES SMD 2512 1.5k 5% 1W")
      (fields
        (field (name "MANUFACTURER") "Bourns")
        (field (name "MANUFACTURER PART NUMBER") "CR2512-JW-152ELF")
      )
      (libsource (lib "Schematic Library - AJMG 2550XD Silver Jubilee") (part "CR2512-JW-152ELF"))
    )
    (comp (ref "R26")
      (value "220k 1%")
      (footprint "R_2010")
      (description "RES SMD 2010 220K 1% 1/2W")
      (fields
        (field (name "MANUFACTURER") "Bourns JW Miller")
        (field (name "MANUFACTURER PART NUMBER") "CHV2010-FX-2203ELF")
      )
      (libsource (lib "Schematic Library - AJMG 2550XD Silver Jubilee") (part "CHV2010-FX-2203ELF"))
    )
    (comp (ref "R27")
      (value "1k2")
      (footprint "R_2512")
      (description "RES SMD 2512 1.2k 5% 1W")
      (fields
        (field (name "MANUFACTURER") "Bourns")
        (field (name "MANUFACTURER PART NUMBER") "CR2512-JW-122ELF")
      )
      (libsource (lib "Schematic Library - AJMG 2550XD Silver Jubilee") (part "CR2512-JW-122ELF"))
    )
    (comp (ref "R28")
      (value "3k 1%")
      (footprint "R_2512")
      (description "RES SMD 2512 3k 1% 1W")
      (fields
        (field (name "MANUFACTURER") "Bourns")
        (field (name "MANUFACTURER PART NUMBER") "CR2512-FX-3001ELF")
      )
      (libsource (lib "Schematic Library - AJMG 2550XD Silver Jubilee") (part "CR2512-FX-3001ELF"))
    )
    (comp (ref "R29")
      (value "330R 2%")
      (footprint "R_MELF_0207")
      (description "RES SMD 0207 330R 2% 1W")
      (fields
        (field (name "MANUFACTURER") "Vishay Beyschlag")
        (field (name "MANUFACTURER PART NUMBER") "CMB02070X3300GB200")
      )
      (libsource (lib "Schematic Library - AJMG 2550XD Silver Jubilee") (part "CMB02070X3300GB200"))
    )
    (comp (ref "R30")
      (value "330R 2%")
      (footprint "R_MELF_0207")
      (description "RES SMD 0207 330R 2% 1W")
      (fields
        (field (name "MANUFACTURER") "Vishay Beyschlag")
        (field (name "MANUFACTURER PART NUMBER") "CMB02070X3300GB200")
      )
      (libsource (lib "Schematic Library - AJMG 2550XD Silver Jubilee") (part "CMB02070X3300GB200"))
    )
    (comp (ref "R31")
      (value "5.6k 5%")
      (footprint "R_2512")
      (description "RES SMD 2512 5.6K 5% 1W")
      (fields
        (field (name "MANUFACTURER") "Bourns")
        (field (name "MANUFACTURER PART NUMBER") "CR2512-JW-562ELF")
      )
      (libsource (lib "Schematic Library - AJMG 2550XD Silver Jubilee") (part "CR2512-JW-562ELF"))
    )
    (comp (ref "R32")
      (value "220k 1%")
      (footprint "R_2010")
      (description "RES SMD 2010 220K 1% 1/2W")
      (fields
        (field (name "MANUFACTURER") "Bourns JW Miller")
        (field (name "MANUFACTURER PART NUMBER") "CHV2010-FX-2203ELF")
      )
      (libsource (lib "Schematic Library - AJMG 2550XD Silver Jubilee") (part "CHV2010-FX-2203ELF"))
    )
    (comp (ref "R33")
      (value "1K 1%")
      (footprint "R_3550")
      (description "RES SMD 3550 1K 1% 5W")
      (fields
        (field (name "MANUFACTURER") "TE Connectivity")
        (field (name "MANUFACTURER PART NUMBER") "35501K0FT")
      )
      (libsource (lib "Schematic Library - AJMG 2550XD Silver Jubilee") (part "35501K0FT"))
    )
    (comp (ref "R34")
      (value "1M 1%")
      (footprint "R_2010")
      (description "RES SMD 2010 1M 1% 1W")
      (fields
        (field (name "MANUFACTURER") "Bourns")
        (field (name "MANUFACTURER PART NUMBER") "CMP2010-FX-1004ELF")
      )
      (libsource (lib "Schematic Library - AJMG 2550XD Silver Jubilee") (part "CMP2010-FX-1004ELF"))
    )
    (comp (ref "R35")
      (value "82k 5%")
      (footprint "R_2512")
      (description "RES SMD 2512 82K 5% 2W")
      (fields
        (field (name "MANUFACTURER") "Bourns")
        (field (name "MANUFACTURER PART NUMBER") "CRM2512-JW-823ELF")
      )
      (libsource (lib "Schematic Library - AJMG 2550XD Silver Jubilee") (part "CRM2512-JW-823ELF"))
    )
    (comp (ref "R36")
      (value "220k 1%")
      (footprint "R_2010")
      (description "RES SMD 2010 220K 1% 1/2W")
      (fields
        (field (name "MANUFACTURER") "Bourns JW Miller")
        (field (name "MANUFACTURER PART NUMBER") "CHV2010-FX-2203ELF")
      )
      (libsource (lib "Schematic Library - AJMG 2550XD Silver Jubilee") (part "CHV2010-FX-2203ELF"))
    )
    (comp (ref "R37")
      (value "1R 1%")
      (footprint "R_4527_MOLDED")
      (description "RES SMD 4527 1R 1% 2W")
      (fields
        (field (name "MANUFACTURER") "Vishay Dale")
        (field (name "MANUFACTURER PART NUMBER") "WSC00021R000FEA")
      )
      (libsource (lib "Schematic Library - AJMG 2550XD Silver Jubilee") (part "WSC00021R000FEA"))
    )
    (comp (ref "R38")
      (value "100k 1%")
      (footprint "R_2010")
      (description "RES SMD 2010 100K 1% 1W")
      (fields
        (field (name "MANUFACTURER") "Bourns")
        (field (name "MANUFACTURER PART NUMBER") "CMP2010-FX-1003ELF")
      )
      (libsource (lib "Schematic Library - AJMG 2550XD Silver Jubilee") (part "CMP2010-FX-1003ELF"))
    )
    (comp (ref "R39")
      (value "100k 1%")
      (footprint "R_2010")
      (description "RES SMD 2010 100K 1% 1W")
      (fields
        (field (name "MANUFACTURER") "Bourns")
        (field (name "MANUFACTURER PART NUMBER") "CMP2010-FX-1003ELF")
      )
      (libsource (lib "Schematic Library - AJMG 2550XD Silver Jubilee") (part "CMP2010-FX-1003ELF"))
    )
    (comp (ref "R40")
      (value "1R 1%")
      (footprint "R_4527_MOLDED")
      (description "RES SMD 4527 1R 1% 2W")
      (fields
        (field (name "MANUFACTURER") "Vishay Dale")
        (field (name "MANUFACTURER PART NUMBER") "WSC00021R000FEA")
      )
      (libsource (lib "Schematic Library - AJMG 2550XD Silver Jubilee") (part "WSC00021R000FEA"))
    )
    (comp (ref "R41")
      (value "330R 2%")
      (footprint "R_MELF_0207")
      (description "RES SMD 0207 330R 2% 1W")
      (fields
        (field (name "MANUFACTURER") "Vishay Beyschlag")
        (field (name "MANUFACTURER PART NUMBER") "CMB02070X3300GB200")
      )
      (libsource (lib "Schematic Library - AJMG 2550XD Silver Jubilee") (part "CMB02070X3300GB200"))
    )
    (comp (ref "R42")
      (value "330R 2%")
      (footprint "R_MELF_0207")
      (description "RES SMD 0207 330R 2% 1W")
      (fields
        (field (name "MANUFACTURER") "Vishay Beyschlag")
        (field (name "MANUFACTURER PART NUMBER") "CMB02070X3300GB200")
      )
      (libsource (lib "Schematic Library - AJMG 2550XD Silver Jubilee") (part "CMB02070X3300GB200"))
    )
    (comp (ref "R43")
      (value "10k 1%")
      (footprint "R_2010")
      (description "RES SMD 2010 10K 1% 1W")
      (fields
        (field (name "MANUFACTURER") "Bourns")
        (field (name "MANUFACTURER PART NUMBER") "CMP2010-FX-1002ELF")
      )
      (libsource (lib "Schematic Library - AJMG 2550XD Silver Jubilee") (part "CMP2010-FX-1002ELF"))
    )
    (comp (ref "R44")
      (value "470R 1%")
      (footprint "R_2512")
      (description "RES SMD 2512 470R 1% 2W")
      (fields
        (field (name "MANUFACTURER") "Bourns")
        (field (name "MANUFACTURER PART NUMBER") "CRM2512-FX-4700ELF")
      )
      (libsource (lib "Schematic Library - AJMG 2550XD Silver Jubilee") (part "CRM2512-FX-4700ELF"))
    )
    (comp (ref "R45")
      (value "100k 1%")
      (footprint "R_2010")
      (description "RES SMD 2010 100K 1% 1W")
      (fields
        (field (name "MANUFACTURER") "Bourns")
        (field (name "MANUFACTURER PART NUMBER") "CMP2010-FX-1003ELF")
      )
      (libsource (lib "Schematic Library - AJMG 2550XD Silver Jubilee") (part "CMP2010-FX-1003ELF"))
    )
    (comp (ref "R46")
      (value "220k 1%")
      (footprint "R_2010")
      (description "RES SMD 2010 220K 1% 1/2W")
      (fields
        (field (name "MANUFACTURER") "Bourns JW Miller")
        (field (name "MANUFACTURER PART NUMBER") "CHV2010-FX-2203ELF")
      )
      (libsource (lib "Schematic Library - AJMG 2550XD Silver Jubilee") (part "CHV2010-FX-2203ELF"))
    )
    (comp (ref "R47")
      (value "10k 1%")
      (footprint "R_2010")
      (description "RES SMD 2010 10K 1% 1W")
      (fields
        (field (name "MANUFACTURER") "Bourns")
        (field (name "MANUFACTURER PART NUMBER") "CMP2010-FX-1002ELF")
      )
      (libsource (lib "Schematic Library - AJMG 2550XD Silver Jubilee") (part "CMP2010-FX-1002ELF"))
    )
    (comp (ref "R48")
      (value "1K 1%")
      (footprint "R_3550")
      (description "RES SMD 3550 1K 1% 5W")
      (fields
        (field (name "MANUFACTURER") "TE Connectivity")
        (field (name "MANUFACTURER PART NUMBER") "35501K0FT")
      )
      (libsource (lib "Schematic Library - AJMG 2550XD Silver Jubilee") (part "35501K0FT"))
    )
    (comp (ref "R49")
      (value "1M 1%")
      (footprint "R_2010")
      (description "RES SMD 2010 1M 1% 1W")
      (fields
        (field (name "MANUFACTURER") "Bourns")
        (field (name "MANUFACTURER PART NUMBER") "CMP2010-FX-1004ELF")
      )
      (libsource (lib "Schematic Library - AJMG 2550XD Silver Jubilee") (part "CMP2010-FX-1004ELF"))
    )
    (comp (ref "R50")
      (value "5.6k 5%")
      (footprint "R_2512")
      (description "RES SMD 2512 5.6K 5% 1W")
      (fields
        (field (name "MANUFACTURER") "Bourns")
        (field (name "MANUFACTURER PART NUMBER") "CR2512-JW-562ELF")
      )
      (libsource (lib "Schematic Library - AJMG 2550XD Silver Jubilee") (part "CR2512-JW-562ELF"))
    )
    (comp (ref "R51")
      (value "100k 1%")
      (footprint "R_2010")
      (description "RES SMD 2010 100K 1% 1W")
      (fields
        (field (name "MANUFACTURER") "Bourns")
        (field (name "MANUFACTURER PART NUMBER") "CMP2010-FX-1003ELF")
      )
      (libsource (lib "Schematic Library - AJMG 2550XD Silver Jubilee") (part "CMP2010-FX-1003ELF"))
    )
    (comp (ref "R52")
      (value "1M 1%")
      (footprint "R_2010")
      (description "RES SMD 2010 1M 1% 1W")
      (fields
        (field (name "MANUFACTURER") "Bourns")
        (field (name "MANUFACTURER PART NUMBER") "CMP2010-FX-1004ELF")
      )
      (libsource (lib "Schematic Library - AJMG 2550XD Silver Jubilee") (part "CMP2010-FX-1004ELF"))
    )
    (comp (ref "R53")
      (value "100k 1%")
      (footprint "R_2010")
      (description "RES SMD 2010 100K 1% 1W")
      (fields
        (field (name "MANUFACTURER") "Bourns")
        (field (name "MANUFACTURER PART NUMBER") "CMP2010-FX-1003ELF")
      )
      (libsource (lib "Schematic Library - AJMG 2550XD Silver Jubilee") (part "CMP2010-FX-1003ELF"))
    )
    (comp (ref "R54")
      (value "470R 1%")
      (footprint "R_2512")
      (description "RES SMD 2512 470R 1% 2W")
      (fields
        (field (name "MANUFACTURER") "Bourns")
        (field (name "MANUFACTURER PART NUMBER") "CRM2512-FX-4700ELF")
      )
      (libsource (lib "Schematic Library - AJMG 2550XD Silver Jubilee") (part "CRM2512-FX-4700ELF"))
    )
    (comp (ref "R55")
      (value "100k 1%")
      (footprint "R_2010")
      (description "RES SMD 2010 100K 1% 1W")
      (fields
        (field (name "MANUFACTURER") "Bourns")
        (field (name "MANUFACTURER PART NUMBER") "CMP2010-FX-1003ELF")
      )
      (libsource (lib "Schematic Library - AJMG 2550XD Silver Jubilee") (part "CMP2010-FX-1003ELF"))
    )
    (comp (ref "R56")
      (value "470R 1%")
      (footprint "R_2512")
      (description "RES SMD 2512 470R 1% 2W")
      (fields
        (field (name "MANUFACTURER") "Bourns")
        (field (name "MANUFACTURER PART NUMBER") "CRM2512-FX-4700ELF")
      )
      (libsource (lib "Schematic Library - AJMG 2550XD Silver Jubilee") (part "CRM2512-FX-4700ELF"))
    )
    (comp (ref "R57")
      (value "4k7 5%")
      (footprint "R_2512_N")
      (description "RES SMD 2512 4.7k 5% 1W")
      (fields (field (name "TOLERANCE") "5 %") (field (name "POWER") "1 W"))
      (libsource (lib "Schematic Library - AJMG 2550XD Silver Jubilee") (part "CMP-1018-00090-1"))
    )
    (comp (ref "R58")
      (value "0 Ohm")
      (footprint "FP-CRCW1210-e3-IPC_B")
      (description "RES SMD 205K OHM 1% 1/2W 1992")
      (libsource (lib "Altium Content Vault") (part "1029c3af85768c4190bb7ad29bc67b5"))
    )
    (comp (ref "R59")
      (value "0 Ohm")
      (footprint "FP-CRCW1210-e3-IPC_B")
      (description "RES SMD 205K OHM 1% 1/2W 1992")
      (libsource (lib "Altium Content Vault") (part "1029c3af85768c4190bb7ad29bc67b5"))
    )
    (comp (ref "R60")
      (value "0 Ohm")
      (footprint "FP-CRCW1210-e3-IPC_B")
      (description "RES SMD 205K OHM 1% 1/2W 1992")
      (libsource (lib "Altium Content Vault") (part "1029c3af85768c4190bb7ad29bc67b5"))
    )
    (comp (ref "V1")
      (value "ECC83")
      (footprint "VT9-PT-2")
      (libsource (lib "Schematic Library - AJMG 2550XD Silver Jubilee") (part "ECC83"))
    )
    (comp (ref "V2")
      (value "ECC83")
      (footprint "VT9-PT-2")
      (libsource (lib "Schematic Library - AJMG 2550XD Silver Jubilee") (part "ECC83"))
    )
    (comp (ref "V3")
      (value "12DW7")
      (footprint "VT9-PT-2")
      (libsource (lib "Schematic Library - AJMG 2550XD Silver Jubilee") (part "12DW7"))
    )
    (comp (ref "V4") (value "EL34") (footprint "VT8-PT-2") (libsource (lib "") (part "EL34_1")))
    (comp (ref "V5") (value "ECC83") (footprint "VT9-PT-2") (libsource (lib "") (part "ECC83_1")))
    (comp (ref "V6")
      (value "EL34")
      (footprint "VT8-PT-2")
      (libsource (lib "Schematic Library - AJMG 2550XD Silver Jubilee") (part "EL34"))
    )
  )
  (nets
    (net (code "1") (name "B+0") (class "Default")
      (node (ref "J17") (pin "2") (pinfunction "2_2") (pintype "passive"))
      (node (ref "J32") (pin "3") (pinfunction "3_3") (pintype "passive"))
    )
    (net (code "2") (name "B+1") (class "Default")
      (node (ref "J14") (pin "3") (pinfunction "3_3") (pintype "passive"))
      (node (ref "J23") (pin "3") (pinfunction "3_3") (pintype "passive"))
      (node (ref "J31") (pin "1") (pinfunction "1_1") (pintype "passive"))
    )
    (net (code "3") (name "B+2") (class "Default")
      (node (ref "J30") (pin "1") (pinfunction "1_1") (pintype "passive"))
      (node (ref "R35") (pin "1") (pinfunction "1_1") (pintype "passive"))
      (node (ref "R45") (pin "2") (pinfunction "2_2") (pintype "passive"))
    )
    (net (code "4") (name "B+3") (class "Default")
      (node (ref "J29") (pin "1") (pinfunction "1_1") (pintype "passive"))
      (node (ref "R2") (pin "2") (pinfunction "2_2") (pintype "passive"))
      (node (ref "R32") (pin "2") (pinfunction "2_2") (pintype "passive"))
      (node (ref "R4") (pin "1") (pinfunction "1_1") (pintype "passive"))
      (node (ref "R6") (pin "2") (pinfunction "2_2") (pintype "passive"))
    )
    (net (code "5") (name "B+4") (class "Default")
      (node (ref "C1") (pin "2") (pinfunction "2_2") (pintype "passive"))
      (node (ref "J28") (pin "1") (pinfunction "1_1") (pintype "passive"))
      (node (ref "R1") (pin "2") (pinfunction "2_2") (pintype "passive"))
      (node (ref "R3") (pin "2") (pinfunction "2_2") (pintype "passive"))
    )
    (net (code "6") (name "BIAS") (class "Default")
      (node (ref "J32") (pin "2") (pinfunction "2_2") (pintype "passive"))
      (node (ref "R36") (pin "1") (pinfunction "1_1") (pintype "passive"))
      (node (ref "R46") (pin "2") (pinfunction "2_2") (pintype "passive"))
    )
    (net (code "7") (name "GND") (class "Default")
      (node (ref "R58") (pin "2") (pinfunction "2_2") (pintype "passive"))
      (node (ref "R59") (pin "1") (pinfunction "1_1") (pintype "passive"))
      (node (ref "R60") (pin "1") (pinfunction "1_1") (pintype "passive"))
    )
    (net (code "8") (name "H1") (class "Default")
      (node (ref "C19") (pin "2") (pinfunction "N_2") (pintype "passive"))
      (node (ref "C20") (pin "2") (pinfunction "N_2") (pintype "passive"))
      (node (ref "C27") (pin "2") (pinfunction "N_2") (pintype "passive"))
      (node (ref "C28") (pin "2") (pinfunction "N_2") (pintype "passive"))
      (node (ref "D10") (pin "1") (pinfunction "A_1") (pintype "passive"))
      (node (ref "D8") (pin "1") (pinfunction "A_1") (pintype "passive"))
      (node (ref "J13") (pin "3") (pinfunction "3_3") (pintype "passive"))
      (node (ref "J16") (pin "1") (pinfunction "1_1") (pintype "passive"))
      (node (ref "J24") (pin "2") (pinfunction "2_2") (pintype "passive"))
      (node (ref "J33") (pin "1") (pinfunction "1_1") (pintype "passive"))
      (node (ref "R29") (pin "1") (pinfunction "1_1") (pintype "passive"))
      (node (ref "R41") (pin "1") (pinfunction "1_1") (pintype "passive"))
      (node (ref "V1") (pin "4") (pinfunction "FB_4") (pintype "passive"))
      (node (ref "V1") (pin "5") (pinfunction "FA_5") (pintype "passive"))
      (node (ref "V2") (pin "4") (pinfunction "FB_4") (pintype "passive"))
      (node (ref "V2") (pin "5") (pinfunction "FA_5") (pintype "passive"))
      (node (ref "V3") (pin "4") (pinfunction "FB_4") (pintype "passive"))
      (node (ref "V3") (pin "5") (pinfunction "FA_5") (pintype "passive"))
      (node (ref "V4") (pin "2") (pinfunction "F_2") (pintype "passive"))
      (node (ref "V5") (pin "4") (pinfunction "FB_4") (pintype "passive"))
      (node (ref "V5") (pin "5") (pinfunction "FA_5") (pintype "passive"))
      (node (ref "V6") (pin "7") (pinfunction "F_7") (pintype "passive"))
    )
    (net (code "9") (name "H2") (class "Default")
      (node (ref "D11") (pin "1") (pinfunction "A_1") (pintype "passive"))
      (node (ref "D9") (pin "1") (pinfunction "A_1") (pintype "passive"))
      (node (ref "J33") (pin "2") (pinfunction "2_2") (pintype "passive"))
      (node (ref "V1") (pin "9") (pinfunction "FC_9") (pintype "passive"))
      (node (ref "V2") (pin "9") (pinfunction "FC_9") (pintype "passive"))
      (node (ref "V3") (pin "9") (pinfunction "FC_9") (pintype "passive"))
      (node (ref "V4") (pin "7") (pinfunction "F_7") (pintype "passive"))
      (node (ref "V5") (pin "9") (pinfunction "FC_9") (pintype "passive"))
      (node (ref "V6") (pin "2") (pinfunction "F_2") (pintype "passive"))
    )
    (net (code "10") (name "Net-(C2-Pad2)") (class "Default")
      (node (ref "C2") (pin "2") (pinfunction "2_2") (pintype "passive"))
      (node (ref "C3") (pin "1") (pinfunction "1_1") (pintype "passive"))
      (node (ref "J10") (pin "1") (pinfunction "1_1") (pintype "passive"))
      (node (ref "J4") (pin "1") (pinfunction "1_1") (pintype "passive"))
    )
    (net (code "11") (name "Net-(C3-Pad2)") (class "Default")
      (node (ref "C3") (pin "2") (pinfunction "2_2") (pintype "passive"))
      (node (ref "K1") (pin "4") (pinfunction "4_4") (pintype "passive"))
      (node (ref "R14") (pin "1") (pinfunction "1_1") (pintype "passive"))
    )
    (net (code "12") (name "Net-(C4-Pad2)") (class "Default")
      (node (ref "C4") (pin "2") (pinfunction "2_2") (pintype "passive"))
      (node (ref "R10") (pin "2") (pinfunction "2_2") (pintype "passive"))
      (node (ref "R7") (pin "1") (pinfunction "1_1") (pintype "passive"))
    )
    (net (code "13") (name "Net-(C5-Pad2)") (class "Default")
      (node (ref "C5") (pin "2") (pinfunction "2_2") (pintype "passive"))
      (node (ref "R8") (pin "2") (pinfunction "2_2") (pintype "passive"))
      (node (ref "R9") (pin "1") (pinfunction "1_1") (pintype "passive"))
    )
    (net (code "14") (name "Net-(C6-Pad1)") (class "Default")
      (node (ref "C6") (pin "1") (pinfunction "1_1") (pintype "passive"))
      (node (ref "R5") (pin "2") (pinfunction "2_2") (pintype "passive"))
    )
    (net (code "15") (name "Net-(C7-Pad2)") (class "Default")
      (node (ref "C7") (pin "2") (pinfunction "2_2") (pintype "passive"))
      (node (ref "J1") (pin "2") (pinfunction "2_2") (pintype "passive"))
    )
    (net (code "16") (name "Net-(C8-Pad2)") (class "Default")
      (node (ref "C8") (pin "2") (pinfunction "2_2") (pintype "passive"))
      (node (ref "J2") (pin "2") (pinfunction "2_2") (pintype "passive"))
    )
    (net (code "17") (name "Net-(C9-Pad1)") (class "Default")
      (node (ref "C9") (pin "1") (pinfunction "1_1") (pintype "passive"))
      (node (ref "J8") (pin "1") (pinfunction "1_1") (pintype "passive"))
    )
    (net (code "18") (name "Net-(C9-Pad2)") (class "Default")
      (node (ref "C9") (pin "2") (pinfunction "2_2") (pintype "passive"))
      (node (ref "R12") (pin "1") (pinfunction "1_1") (pintype "passive"))
      (node (ref "R19") (pin "2") (pinfunction "2_2") (pintype "passive"))
    )
    (net (code "19") (name "Net-(C11-Pad1)") (class "Default")
      (node (ref "C11") (pin "1") (pinfunction "1_1") (pintype "passive"))
      (node (ref "J11") (pin "1") (pinfunction "1_1") (pintype "passive"))
      (node (ref "J11") (pin "2") (pinfunction "2_2") (pintype "passive"))
    )
    (net (code "20") (name "Net-(C11-Pad2)") (class "Default")
      (node (ref "C11") (pin "2") (pinfunction "2_2") (pintype "passive"))
      (node (ref "J1") (pin "1") (pinfunction "1_1") (pintype "passive"))
      (node (ref "R5") (pin "1") (pinfunction "1_1") (pintype "passive"))
    )
    (net (code "21") (name "Net-(C12-Pad1)") (class "Default")
      (node (ref "C12") (pin "1") (pinfunction "1_1") (pintype "passive"))
      (node (ref "J7") (pin "3") (pinfunction "3_3") (pintype "passive"))
    )
    (net (code "22") (name "Net-(C12-Pad2)") (class "Default")
      (node (ref "C12") (pin "2") (pinfunction "2_2") (pintype "passive"))
      (node (ref "J9") (pin "2") (pinfunction "2_2") (pintype "passive"))
    )
    (net (code "23") (name "Net-(C14-P)") (class "Default")
      (node (ref "C10") (pin "1") (pinfunction "1_1") (pintype "passive"))
      (node (ref "C14") (pin "1") (pinfunction "P_1") (pintype "passive"))
      (node (ref "R24") (pin "2") (pinfunction "2_2") (pintype "passive"))
      (node (ref "V1") (pin "8") (pinfunction "K1_8") (pintype "passive"))
    )
    (net (code "24") (name "Net-(C15-P)") (class "Default")
      (node (ref "C15") (pin "1") (pinfunction "P_1") (pintype "passive"))
      (node (ref "R25") (pin "2") (pinfunction "2_2") (pintype "passive"))
      (node (ref "V1") (pin "3") (pinfunction "K2_3") (pintype "passive"))
    )
    (net (code "25") (name "Net-(C17-P)") (class "Default")
      (node (ref "C17") (pin "1") (pinfunction "P_1") (pintype "passive"))
      (node (ref "R27") (pin "2") (pinfunction "2_2") (pintype "passive"))
      (node (ref "V3") (pin "3") (pinfunction "K2_3") (pintype "passive"))
    )
    (net (code "26") (name "Net-(C19-P)") (class "Default")
      (node (ref "C19") (pin "1") (pinfunction "P_1") (pintype "passive"))
      (node (ref "D8") (pin "2") (pinfunction "C_2") (pintype "passive"))
      (node (ref "J13") (pin "2") (pinfunction "2_2") (pintype "passive"))
      (node (ref "K1") (pin "16") (pinfunction "16_16") (pintype "passive"))
      (node (ref "R30") (pin "2") (pinfunction "2_2") (pintype "passive"))
    )
    (net (code "27") (name "Net-(C20-P)") (class "Default")
      (node (ref "C20") (pin "1") (pinfunction "P_1") (pintype "passive"))
      (node (ref "D9") (pin "2") (pinfunction "C_2") (pintype "passive"))
      (node (ref "K1") (pin "1") (pinfunction "1_1") (pintype "passive"))
    )
    (net (code "28") (name "Net-(C21-Pad2)") (class "Default")
      (node (ref "C21") (pin "2") (pinfunction "2_2") (pintype "passive"))
      (node (ref "C25") (pin "2") (pinfunction "2_2") (pintype "passive"))
      (node (ref "R31") (pin "1") (pinfunction "1_1") (pintype "passive"))
      (node (ref "R36") (pin "2") (pinfunction "2_2") (pintype "passive"))
    )
    (net (code "29") (name "Net-(C22-Pad2)") (class "Default")
      (node (ref "C22") (pin "2") (pinfunction "2_2") (pintype "passive"))
      (node (ref "R38") (pin "2") (pinfunction "2_2") (pintype "passive"))
    )
    (net (code "30") (name "Net-(C23-Pad2)") (class "Default")
      (node (ref "C23") (pin "2") (pinfunction "2_2") (pintype "passive"))
      (node (ref "C24") (pin "1") (pinfunction "1_1") (pintype "passive"))
      (node (ref "J20") (pin "2") (pinfunction "2_2") (pintype "passive"))
      (node (ref "R39") (pin "2") (pinfunction "2_2") (pintype "passive"))
    )
    (net (code "31") (name "Net-(C24-Pad2)") (class "Default")
      (node (ref "C24") (pin "2") (pinfunction "2_2") (pintype "passive"))
      (node (ref "C32") (pin "2") (pinfunction "2_2") (pintype "passive"))
      (node (ref "J19") (pin "1") (pinfunction "1_1") (pintype "passive"))
    )
    (net (code "32") (name "Net-(C25-Pad1)") (class "Default")
      (node (ref "C25") (pin "1") (pinfunction "1_1") (pintype "passive"))
      (node (ref "C31") (pin "2") (pinfunction "2_2") (pintype "passive"))
      (node (ref "R46") (pin "1") (pinfunction "1_1") (pintype "passive"))
      (node (ref "R50") (pin "1") (pinfunction "1_1") (pintype "passive"))
    )
    (net (code "33") (name "Net-(C26-Pad1)") (class "Default")
      (node (ref "C26") (pin "1") (pinfunction "1_1") (pintype "passive"))
      (node (ref "J20") (pin "1") (pinfunction "1_1") (pintype "passive"))
    )
    (net (code "34") (name "Net-(C27-P)") (class "Default")
      (node (ref "C27") (pin "1") (pinfunction "P_1") (pintype "passive"))
      (node (ref "D10") (pin "2") (pinfunction "C_2") (pintype "passive"))
      (node (ref "J13") (pin "1") (pinfunction "1_1") (pintype "passive"))
      (node (ref "K2") (pin "16") (pinfunction "16_16") (pintype "passive"))
      (node (ref "R42") (pin "2") (pinfunction "2_2") (pintype "passive"))
    )
    (net (code "35") (name "Net-(C28-P)") (class "Default")
      (node (ref "C28") (pin "1") (pinfunction "P_1") (pintype "passive"))
      (node (ref "D11") (pin "2") (pinfunction "C_2") (pintype "passive"))
      (node (ref "K2") (pin "1") (pinfunction "1_1") (pintype "passive"))
    )
    (net (code "36") (name "Net-(C29-Pad1)") (class "Default")
      (node (ref "C29") (pin "1") (pinfunction "1_1") (pintype "passive"))
      (node (ref "J22") (pin "1") (pinfunction "1_1") (pintype "passive"))
    )
    (net (code "37") (name "Net-(C30-Pad1)") (class "Default")
      (node (ref "C30") (pin "1") (pinfunction "1_1") (pintype "passive"))
      (node (ref "C34") (pin "2") (pinfunction "2_2") (pintype "passive"))
      (node (ref "R39") (pin "1") (pinfunction "1_1") (pintype "passive"))
    )
    (net (code "38") (name "Net-(C30-Pad2)") (class "Default")
      (node (ref "C30") (pin "2") (pinfunction "2_2") (pintype "passive"))
      (node (ref "R47") (pin "1") (pinfunction "1_1") (pintype "passive"))
    )
    (net (code "39") (name "Net-(C32-Pad1)") (class "Default")
      (node (ref "C32") (pin "1") (pinfunction "1_1") (pintype "passive"))
      (node (ref "J25") (pin "1") (pinfunction "1_1") (pintype "passive"))
    )
    (net (code "40") (name "Net-(C33-Pad2)") (class "Default")
      (node (ref "C33") (pin "2") (pinfunction "2_2") (pintype "passive"))
      (node (ref "J19") (pin "3") (pinfunction "3_3") (pintype "passive"))
      (node (ref "R47") (pin "2") (pinfunction "2_2") (pintype "passive"))
      (node (ref "R51") (pin "2") (pinfunction "2_2") (pintype "passive"))
    )
    (net (code "41") (name "Net-(C34-Pad1)") (class "Default")
      (node (ref "C34") (pin "1") (pinfunction "1_1") (pintype "passive"))
      (node (ref "J25") (pin "2") (pinfunction "2_2") (pintype "passive"))
    )
    (net (code "42") (name "Net-(C35-Pad1)") (class "Default")
      (node (ref "C35") (pin "1") (pinfunction "1_1") (pintype "passive"))
      (node (ref "C36") (pin "1") (pinfunction "1_1") (pintype "passive"))
      (node (ref "R43") (pin "1") (pinfunction "1_1") (pintype "passive"))
      (node (ref "R55") (pin "1") (pinfunction "1_1") (pintype "passive"))
      (node (ref "R57") (pin "1") (pinfunction "1_1") (pintype "passive"))
    )
    (net (code "43") (name "Net-(C36-Pad2)") (class "Default")
      (node (ref "C36") (pin "2") (pinfunction "2_2") (pintype "passive"))
      (node (ref "J27") (pin "1") (pinfunction "1_1") (pintype "passive"))
    )
    (net (code "44") (name "Net-(D1-A)") (class "Default")
      (node (ref "C13") (pin "2") (pinfunction "2_2") (pintype "passive"))
      (node (ref "D1") (pin "1") (pinfunction "A_1") (pintype "passive"))
      (node (ref "D2") (pin "2") (pinfunction "C_2") (pintype "passive"))
      (node (ref "J5") (pin "1") (pinfunction "1_1") (pintype "passive"))
      (node (ref "K1") (pin "9") (pinfunction "9_9") (pintype "passive"))
      (node (ref "R7") (pin "2") (pinfunction "2_2") (pintype "passive"))
    )
    (net (code "45") (name "Net-(D1-C)") (class "Default")
      (node (ref "D1") (pin "2") (pinfunction "C_2") (pintype "passive"))
      (node (ref "D2") (pin "1") (pinfunction "A_1") (pintype "passive"))
      (node (ref "D3") (pin "1") (pinfunction "A_1") (pintype "passive"))
      (node (ref "D4") (pin "2") (pinfunction "C_2") (pintype "passive"))
    )
    (net (code "46") (name "Net-(D3-C)") (class "Default")
      (node (ref "D3") (pin "2") (pinfunction "C_2") (pintype "passive"))
      (node (ref "D5") (pin "1") (pinfunction "A_1") (pintype "passive"))
    )
    (net (code "47") (name "Net-(D6-A)") (class "Default")
      (node (ref "C16") (pin "2") (pinfunction "2_2") (pintype "passive"))
      (node (ref "D6") (pin "1") (pinfunction "A_1") (pintype "passive"))
      (node (ref "D7") (pin "2") (pinfunction "C_2") (pintype "passive"))
      (node (ref "J12") (pin "2") (pinfunction "2_2") (pintype "passive"))
      (node (ref "R16") (pin "1") (pinfunction "1_1") (pintype "passive"))
    )
    (net (code "48") (name "Net-(J3-Pad2)") (class "Default")
      (node (ref "J3") (pin "2") (pinfunction "2_2") (pintype "passive"))
      (node (ref "R13") (pin "2") (pinfunction "2_2") (pintype "passive"))
    )
    (net (code "49") (name "Net-(J4-Pad2)") (class "Default")
      (node (ref "J4") (pin "2") (pinfunction "2_2") (pintype "passive"))
      (node (ref "K1") (pin "8") (pinfunction "8_8") (pintype "passive"))
    )
    (net (code "50") (name "Net-(J5-Pad2)") (class "Default")
      (node (ref "J5") (pin "2") (pinfunction "2_2") (pintype "passive"))
      (node (ref "R11") (pin "1") (pinfunction "1_1") (pintype "passive"))
    )
    (net (code "51") (name "Net-(J6-Pad2)") (class "Default")
      (node (ref "J6") (pin "2") (pinfunction "2_2") (pintype "passive"))
      (node (ref "R21") (pin "2") (pinfunction "2_2") (pintype "passive"))
    )
    (net (code "52") (name "Net-(J7-Pad2)") (class "Default")
      (node (ref "J7") (pin "2") (pinfunction "2_2") (pintype "passive"))
      (node (ref "R26") (pin "2") (pinfunction "2_2") (pintype "passive"))
    )
    (net (code "53") (name "Net-(J10-Pad2)") (class "Default")
      (node (ref "J10") (pin "2") (pinfunction "2_2") (pintype "passive"))
      (node (ref "K1") (pin "6") (pinfunction "6_6") (pintype "passive"))
    )
    (net (code "54") (name "Net-(J12-Pad1)") (class "Default")
      (node (ref "J12") (pin "1") (pinfunction "1_1") (pintype "passive"))
      (node (ref "K1") (pin "11") (pinfunction "11_11") (pintype "passive"))
      (node (ref "R10") (pin "1") (pinfunction "1_1") (pintype "passive"))
      (node (ref "R17") (pin "2") (pinfunction "2_2") (pintype "passive"))
      (node (ref "R22") (pin "1") (pinfunction "1_1") (pintype "passive"))
    )
    (net (code "55") (name "Net-(J14-Pad2)") (class "Default")
      (node (ref "J14") (pin "2") (pinfunction "2_2") (pintype "passive"))
      (node (ref "R33") (pin "1") (pinfunction "1_1") (pintype "passive"))
    )
    (net (code "56") (name "Net-(J15-Pad1)") (class "Default")
      (node (ref "J15") (pin "1") (pinfunction "1_1") (pintype "passive"))
      (node (ref "J16") (pin "2") (pinfunction "2_2") (pintype "passive"))
    )
    (net (code "57") (name "Net-(J15-Pad2)") (class "Default")
      (node (ref "J15") (pin "2") (pinfunction "2_2") (pintype "passive"))
      (node (ref "J24") (pin "1") (pinfunction "1_1") (pintype "passive"))
    )
    (net (code "58") (name "Net-(J18-Pad2)") (class "Default")
      (node (ref "J18") (pin "2") (pinfunction "2_2") (pintype "passive"))
      (node (ref "R55") (pin "2") (pinfunction "2_2") (pintype "passive"))
    )
    (net (code "59") (name "Net-(J19-Pad2)") (class "Default")
      (node (ref "J19") (pin "2") (pinfunction "2_2") (pintype "passive"))
      (node (ref "J21") (pin "1") (pinfunction "1_1") (pintype "passive"))
      (node (ref "J9") (pin "3") (pinfunction "3_3") (pintype "passive"))
    )
    (net (code "60") (name "Net-(J20-Pad3)") (class "Default")
      (node (ref "J20") (pin "3") (pinfunction "3_3") (pintype "passive"))
      (node (ref "R53") (pin "2") (pinfunction "2_2") (pintype "passive"))
    )
    (net (code "61") (name "Net-(J21-Pad2)") (class "Default")
      (node (ref "J21") (pin "2") (pinfunction "2_2") (pintype "passive"))
      (node (ref "R38") (pin "1") (pinfunction "1_1") (pintype "passive"))
    )
    (net (code "62") (name "Net-(J22-Pad2)") (class "Default")
      (node (ref "J22") (pin "2") (pinfunction "2_2") (pintype "passive"))
      (node (ref "J6") (pin "1") (pinfunction "1_1") (pintype "passive"))
      (node (ref "R20") (pin "2") (pinfunction "2_2") (pintype "passive"))
      (node (ref "R8") (pin "1") (pinfunction "1_1") (pintype "passive"))
    )
    (net (code "63") (name "Net-(J23-Pad2)") (class "Default")
      (node (ref "J23") (pin "2") (pinfunction "2_2") (pintype "passive"))
      (node (ref "R48") (pin "2") (pinfunction "2_2") (pintype "passive"))
    )
    (net (code "64") (name "Net-(J26-Pad1)") (class "Default")
      (node (ref "J26") (pin "1") (pinfunction "1_1") (pintype "passive"))
      (node (ref "J26") (pin "2") (pinfunction "2_2") (pintype "passive"))
      (node (ref "R51") (pin "1") (pinfunction "1_1") (pintype "passive"))
    )
    (net (code "65") (name "Net-(J27-Pad2)") (class "Default")
      (node (ref "J27") (pin "2") (pinfunction "2_2") (pintype "passive"))
      (node (ref "R57") (pin "2") (pinfunction "2_2") (pintype "passive"))
    )
    (net (code "66") (name "Net-(J27-Pad3)") (class "Default")
      (node (ref "J27") (pin "3") (pinfunction "3_3") (pintype "passive"))
      (node (ref "R56") (pin "1") (pinfunction "1_1") (pintype "passive"))
    )
    (net (code "67") (name "Net-(P1-Pad1)") (class "Default")
      (node (ref "P1") (pin "1") (pinfunction "1_1") (pintype "passive"))
      (node (ref "R30") (pin "1") (pinfunction "1_1") (pintype "passive"))
    )
    (net (code "68") (name "Net-(P1-Pad2)") (class "Default")
      (node (ref "P1") (pin "2") (pinfunction "2_2") (pintype "passive"))
      (node (ref "R29") (pin "2") (pinfunction "2_2") (pintype "passive"))
    )
    (net (code "69") (name "Net-(P2-Pad1)") (class "Default")
      (node (ref "P2") (pin "1") (pinfunction "1_1") (pintype "passive"))
      (node (ref "R42") (pin "1") (pinfunction "1_1") (pintype "passive"))
    )
    (net (code "70") (name "Net-(P2-Pad2)") (class "Default")
      (node (ref "P2") (pin "2") (pinfunction "2_2") (pintype "passive"))
      (node (ref "R41") (pin "2") (pinfunction "2_2") (pintype "passive"))
    )
    (net (code "71") (name "Net-(R15-Pad1)") (class "Default")
      (node (ref "R15") (pin "1") (pinfunction "1_1") (pintype "passive"))
      (node (ref "R17") (pin "1") (pinfunction "1_1") (pintype "passive"))
    )
    (net (code "72") (name "Net-(R34-Pad1)") (class "Default")
      (node (ref "R34") (pin "1") (pinfunction "1_1") (pintype "passive"))
      (node (ref "R43") (pin "2") (pinfunction "2_2") (pintype "passive"))
      (node (ref "R44") (pin "1") (pinfunction "1_1") (pintype "passive"))
      (node (ref "R49") (pin "2") (pinfunction "2_2") (pintype "passive"))
    )
    (net (code "73") (name "Net-(V1A-A1)") (class "Default")
      (node (ref "C10") (pin "2") (pinfunction "2_2") (pintype "passive"))
      (node (ref "C2") (pin "1") (pinfunction "1_1") (pintype "passive"))
      (node (ref "R1") (pin "1") (pinfunction "1_1") (pintype "passive"))
      (node (ref "V1") (pin "6") (pinfunction "A1_6") (pintype "passive"))
    )
    (net (code "74") (name "Net-(V1A-G1)") (class "Default")
      (node (ref "R12") (pin "2") (pinfunction "2_2") (pintype "passive"))
      (node (ref "V1") (pin "7") (pinfunction "G1_7") (pintype "passive"))
    )
    (net (code "75") (name "Net-(V1B-A2)") (class "Default")
      (node (ref "C1") (pin "1") (pinfunction "1_1") (pintype "passive"))
      (node (ref "C4") (pin "1") (pinfunction "1_1") (pintype "passive"))
      (node (ref "R3") (pin "1") (pinfunction "1_1") (pintype "passive"))
      (node (ref "V1") (pin "1") (pinfunction "A2_1") (pintype "passive"))
    )
    (net (code "76") (name "Net-(V1B-G2)") (class "Default")
      (node (ref "R14") (pin "2") (pinfunction "2_2") (pintype "passive"))
      (node (ref "R22") (pin "2") (pinfunction "2_2") (pintype "passive"))
      (node (ref "V1") (pin "2") (pinfunction "G2_2") (pintype "passive"))
    )
    (net (code "77") (name "Net-(V2A-A1)") (class "Default")
      (node (ref "C5") (pin "1") (pinfunction "1_1") (pintype "passive"))
      (node (ref "R2") (pin "1") (pinfunction "1_1") (pintype "passive"))
      (node (ref "V2") (pin "6") (pinfunction "A1_6") (pintype "passive"))
    )
    (net (code "78") (name "Net-(V2A-G1)") (class "Default")
      (node (ref "R11") (pin "2") (pinfunction "2_2") (pintype "passive"))
      (node (ref "R15") (pin "2") (pinfunction "2_2") (pintype "passive"))
      (node (ref "R16") (pin "2") (pinfunction "2_2") (pintype "passive"))
      (node (ref "R9") (pin "2") (pinfunction "2_2") (pintype "passive"))
      (node (ref "V2") (pin "7") (pinfunction "G1_7") (pintype "passive"))
    )
    (net (code "79") (name "Net-(V2A-K1)") (class "Default")
      (node (ref "R23") (pin "2") (pinfunction "2_2") (pintype "passive"))
      (node (ref "V2") (pin "8") (pinfunction "K1_8") (pintype "passive"))
    )
    (net (code "80") (name "Net-(V2B-A2)") (class "Default")
      (node (ref "C23") (pin "1") (pinfunction "1_1") (pintype "passive"))
      (node (ref "C26") (pin "2") (pinfunction "2_2") (pintype "passive"))
      (node (ref "J9") (pin "1") (pinfunction "1_1") (pintype "passive"))
      (node (ref "R32") (pin "1") (pinfunction "1_1") (pintype "passive"))
      (node (ref "V2") (pin "1") (pinfunction "A2_1") (pintype "passive"))
    )
    (net (code "81") (name "Net-(V2B-G2)") (class "Default")
      (node (ref "C29") (pin "2") (pinfunction "2_2") (pintype "passive"))
      (node (ref "R52") (pin "2") (pinfunction "2_2") (pintype "passive"))
      (node (ref "V2") (pin "2") (pinfunction "G2_2") (pintype "passive"))
    )
    (net (code "82") (name "Net-(V2B-K2)") (class "Default")
      (node (ref "R54") (pin "2") (pinfunction "2_2") (pintype "passive"))
      (node (ref "V2") (pin "3") (pinfunction "K2_3") (pintype "passive"))
    )
    (net (code "83") (name "Net-(V3A-A1)") (class "Default")
      (node (ref "C7") (pin "1") (pinfunction "1_1") (pintype "passive"))
      (node (ref "R4") (pin "2") (pinfunction "2_2") (pintype "passive"))
      (node (ref "V3") (pin "6") (pinfunction "A1_6") (pintype "passive"))
    )
    (net (code "84") (name "Net-(V3A-G1)") (class "Default")
      (node (ref "K2") (pin "6") (pinfunction "6_6") (pintype "passive"))
      (node (ref "R13") (pin "1") (pinfunction "1_1") (pintype "passive"))
      (node (ref "R18") (pin "2") (pinfunction "2_2") (pintype "passive"))
      (node (ref "V3") (pin "7") (pinfunction "G1_7") (pintype "passive"))
    )
    (net (code "85") (name "Net-(V3A-K1)") (class "Default")
      (node (ref "C18") (pin "2") (pinfunction "2_2") (pintype "passive"))
      (node (ref "R28") (pin "2") (pinfunction "2_2") (pintype "passive"))
      (node (ref "V3") (pin "8") (pinfunction "K1_8") (pintype "passive"))
    )
    (net (code "86") (name "Net-(V3B-A2)") (class "Default")
      (node (ref "C8") (pin "1") (pinfunction "1_1") (pintype "passive"))
      (node (ref "R6") (pin "1") (pinfunction "1_1") (pintype "passive"))
      (node (ref "V3") (pin "1") (pinfunction "A2_1") (pintype "passive"))
    )
    (net (code "87") (name "Net-(V3B-G2)") (class "Default")
      (node (ref "J7") (pin "1") (pinfunction "1_1") (pintype "passive"))
      (node (ref "V3") (pin "2") (pinfunction "G2_2") (pintype "passive"))
    )
    (net (code "88") (name "Net-(V4A-A)") (class "Default")
      (node (ref "J14") (pin "1") (pinfunction "1_1") (pintype "passive"))
      (node (ref "J17") (pin "1") (pinfunction "1_1") (pintype "passive"))
      (node (ref "V4") (pin "3") (pinfunction "A_3") (pintype "passive"))
    )
    (net (code "89") (name "Net-(V4A-G1)") (class "Default")
      (node (ref "R31") (pin "2") (pinfunction "2_2") (pintype "passive"))
      (node (ref "V4") (pin "5") (pinfunction "G1_5") (pintype "passive"))
    )
    (net (code "90") (name "Net-(V4A-G2)") (class "Default")
      (node (ref "R33") (pin "2") (pinfunction "2_2") (pintype "passive"))
      (node (ref "V4") (pin "4") (pinfunction "G2_4") (pintype "passive"))
    )
    (net (code "91") (name "Net-(V4A-K)") (class "Default")
      (node (ref "R37") (pin "2") (pinfunction "2_2") (pintype "passive"))
      (node (ref "V4") (pin "8") (pinfunction "K_8") (pintype "passive"))
    )
    (net (code "92") (name "Net-(V5A-A1)") (class "Default")
      (node (ref "C21") (pin "1") (pinfunction "1_1") (pintype "passive"))
      (node (ref "R35") (pin "2") (pinfunction "2_2") (pintype "passive"))
      (node (ref "V5") (pin "6") (pinfunction "A1_6") (pintype "passive"))
    )
    (net (code "93") (name "Net-(V5A-G1)") (class "Default")
      (node (ref "C22") (pin "1") (pinfunction "1_1") (pintype "passive"))
      (node (ref "C6") (pin "2") (pinfunction "2_2") (pintype "passive"))
      (node (ref "R34") (pin "2") (pinfunction "2_2") (pintype "passive"))
      (node (ref "V5") (pin "7") (pinfunction "G1_7") (pintype "passive"))
    )
    (net (code "94") (name "Net-(V5A-K1)") (class "Default")
      (node (ref "R44") (pin "2") (pinfunction "2_2") (pintype "passive"))
      (node (ref "V5") (pin "3") (pinfunction "K2_3") (pintype "passive"))
      (node (ref "V5") (pin "8") (pinfunction "K1_8") (pintype "passive"))
    )
    (net (code "95") (name "Net-(V5B-A2)") (class "Default")
      (node (ref "C31") (pin "1") (pinfunction "1_1") (pintype "passive"))
      (node (ref "R45") (pin "1") (pinfunction "1_1") (pintype "passive"))
      (node (ref "V5") (pin "1") (pinfunction "A2_1") (pintype "passive"))
    )
    (net (code "96") (name "Net-(V5B-G2)") (class "Default")
      (node (ref "C35") (pin "2") (pinfunction "2_2") (pintype "passive"))
      (node (ref "R49") (pin "1") (pinfunction "1_1") (pintype "passive"))
      (node (ref "V5") (pin "2") (pinfunction "G2_2") (pintype "passive"))
    )
    (net (code "97") (name "Net-(V6A-A)") (class "Default")
      (node (ref "J17") (pin "3") (pinfunction "3_3") (pintype "passive"))
      (node (ref "J23") (pin "1") (pinfunction "1_1") (pintype "passive"))
      (node (ref "V6") (pin "3") (pinfunction "A_3") (pintype "passive"))
    )
    (net (code "98") (name "Net-(V6A-G1)") (class "Default")
      (node (ref "R50") (pin "2") (pinfunction "2_2") (pintype "passive"))
      (node (ref "V6") (pin "5") (pinfunction "G1_5") (pintype "passive"))
    )
    (net (code "99") (name "Net-(V6A-G2)") (class "Default")
      (node (ref "R48") (pin "1") (pinfunction "1_1") (pintype "passive"))
      (node (ref "V6") (pin "4") (pinfunction "G2_4") (pintype "passive"))
    )
    (net (code "100") (name "Net-(V6A-K)") (class "Default")
      (node (ref "R40") (pin "1") (pinfunction "1_1") (pintype "passive"))
      (node (ref "V6") (pin "8") (pinfunction "K_8") (pintype "passive"))
    )
    (net (code "101") (name "PI_GND") (class "Default")
      (node (ref "J30") (pin "2") (pinfunction "2_2") (pintype "passive"))
      (node (ref "J31") (pin "2") (pinfunction "2_2") (pintype "passive"))
      (node (ref "R56") (pin "2") (pinfunction "2_2") (pintype "passive"))
      (node (ref "R60") (pin "2") (pinfunction "2_2") (pintype "passive"))
    )
    (net (code "102") (name "PRE_GND") (class "Default")
      (node (ref "C13") (pin "1") (pinfunction "1_1") (pintype "passive"))
      (node (ref "C14") (pin "2") (pinfunction "N_2") (pintype "passive"))
      (node (ref "C15") (pin "2") (pinfunction "N_2") (pintype "passive"))
      (node (ref "C16") (pin "1") (pinfunction "1_1") (pintype "passive"))
      (node (ref "C17") (pin "2") (pinfunction "N_2") (pintype "passive"))
      (node (ref "C18") (pin "1") (pinfunction "1_1") (pintype "passive"))
      (node (ref "C33") (pin "1") (pinfunction "1_1") (pintype "passive"))
      (node (ref "D4") (pin "1") (pinfunction "A_1") (pintype "passive"))
      (node (ref "D5") (pin "2") (pinfunction "C_2") (pintype "passive"))
      (node (ref "D6") (pin "2") (pinfunction "C_2") (pintype "passive"))
      (node (ref "D7") (pin "1") (pinfunction "A_1") (pintype "passive"))
      (node (ref "J1") (pin "3") (pinfunction "3_3") (pintype "passive"))
      (node (ref "J10") (pin "3") (pinfunction "3_3") (pintype "passive"))
      (node (ref "J11") (pin "3") (pinfunction "3_3") (pintype "passive"))
      (node (ref "J2") (pin "1") (pinfunction "1_1") (pintype "passive"))
      (node (ref "J21") (pin "3") (pinfunction "3_3") (pintype "passive"))
      (node (ref "J22") (pin "3") (pinfunction "3_3") (pintype "passive"))
      (node (ref "J25") (pin "3") (pinfunction "3_3") (pintype "passive"))
      (node (ref "J26") (pin "3") (pinfunction "3_3") (pintype "passive"))
      (node (ref "J28") (pin "2") (pinfunction "2_2") (pintype "passive"))
      (node (ref "J29") (pin "2") (pinfunction "2_2") (pintype "passive"))
      (node (ref "J3") (pin "1") (pinfunction "1_1") (pintype "passive"))
      (node (ref "J4") (pin "3") (pinfunction "3_3") (pintype "passive"))
      (node (ref "J5") (pin "3") (pinfunction "3_3") (pintype "passive"))
      (node (ref "J8") (pin "2") (pinfunction "2_2") (pintype "passive"))
      (node (ref "K1") (pin "13") (pinfunction "13_13") (pintype "passive"))
      (node (ref "K2") (pin "4") (pinfunction "4_4") (pintype "passive"))
      (node (ref "R18") (pin "1") (pinfunction "1_1") (pintype "passive"))
      (node (ref "R19") (pin "1") (pinfunction "1_1") (pintype "passive"))
      (node (ref "R20") (pin "1") (pinfunction "1_1") (pintype "passive"))
      (node (ref "R21") (pin "1") (pinfunction "1_1") (pintype "passive"))
      (node (ref "R23") (pin "1") (pinfunction "1_1") (pintype "passive"))
      (node (ref "R24") (pin "1") (pinfunction "1_1") (pintype "passive"))
      (node (ref "R25") (pin "1") (pinfunction "1_1") (pintype "passive"))
      (node (ref "R26") (pin "1") (pinfunction "1_1") (pintype "passive"))
      (node (ref "R27") (pin "1") (pinfunction "1_1") (pintype "passive"))
      (node (ref "R28") (pin "1") (pinfunction "1_1") (pintype "passive"))
      (node (ref "R52") (pin "1") (pinfunction "1_1") (pintype "passive"))
      (node (ref "R53") (pin "1") (pinfunction "1_1") (pintype "passive"))
      (node (ref "R54") (pin "1") (pinfunction "1_1") (pintype "passive"))
      (node (ref "R58") (pin "1") (pinfunction "1_1") (pintype "passive"))
    )
    (net (code "103") (name "PWR_GND") (class "Default")
      (node (ref "J18") (pin "1") (pinfunction "1_1") (pintype "passive"))
      (node (ref "J32") (pin "1") (pinfunction "1_1") (pintype "passive"))
      (node (ref "R37") (pin "1") (pinfunction "1_1") (pintype "passive"))
      (node (ref "R40") (pin "2") (pinfunction "2_2") (pintype "passive"))
      (node (ref "R59") (pin "2") (pinfunction "2_2") (pintype "passive"))
      (node (ref "V4") (pin "1") (pinfunction "G3_1") (pintype "passive"))
      (node (ref "V6") (pin "1") (pinfunction "G3_1") (pintype "passive"))
    )
    (net (code "104") (name "unconnected-(K2-Pad8)") (class "Default")
      (node (ref "K2") (pin "8") (pinfunction "8_8") (pintype "passive"))
    )
    (net (code "105") (name "unconnected-(K2-Pad9)") (class "Default")
      (node (ref "K2") (pin "9") (pinfunction "9_9") (pintype "passive"))
    )
    (net (code "106") (name "unconnected-(K2-Pad11)") (class "Default")
      (node (ref "K2") (pin "11") (pinfunction "11_11") (pintype "passive"))
    )
    (net (code "107") (name "unconnected-(K2-Pad13)") (class "Default")
      (node (ref "K2") (pin "13") (pinfunction "13_13") (pintype "passive"))
    )
  )
)
